# light-plate_leds_v1_0.net
KiCad netlist of a schematic drawn in EAGLE
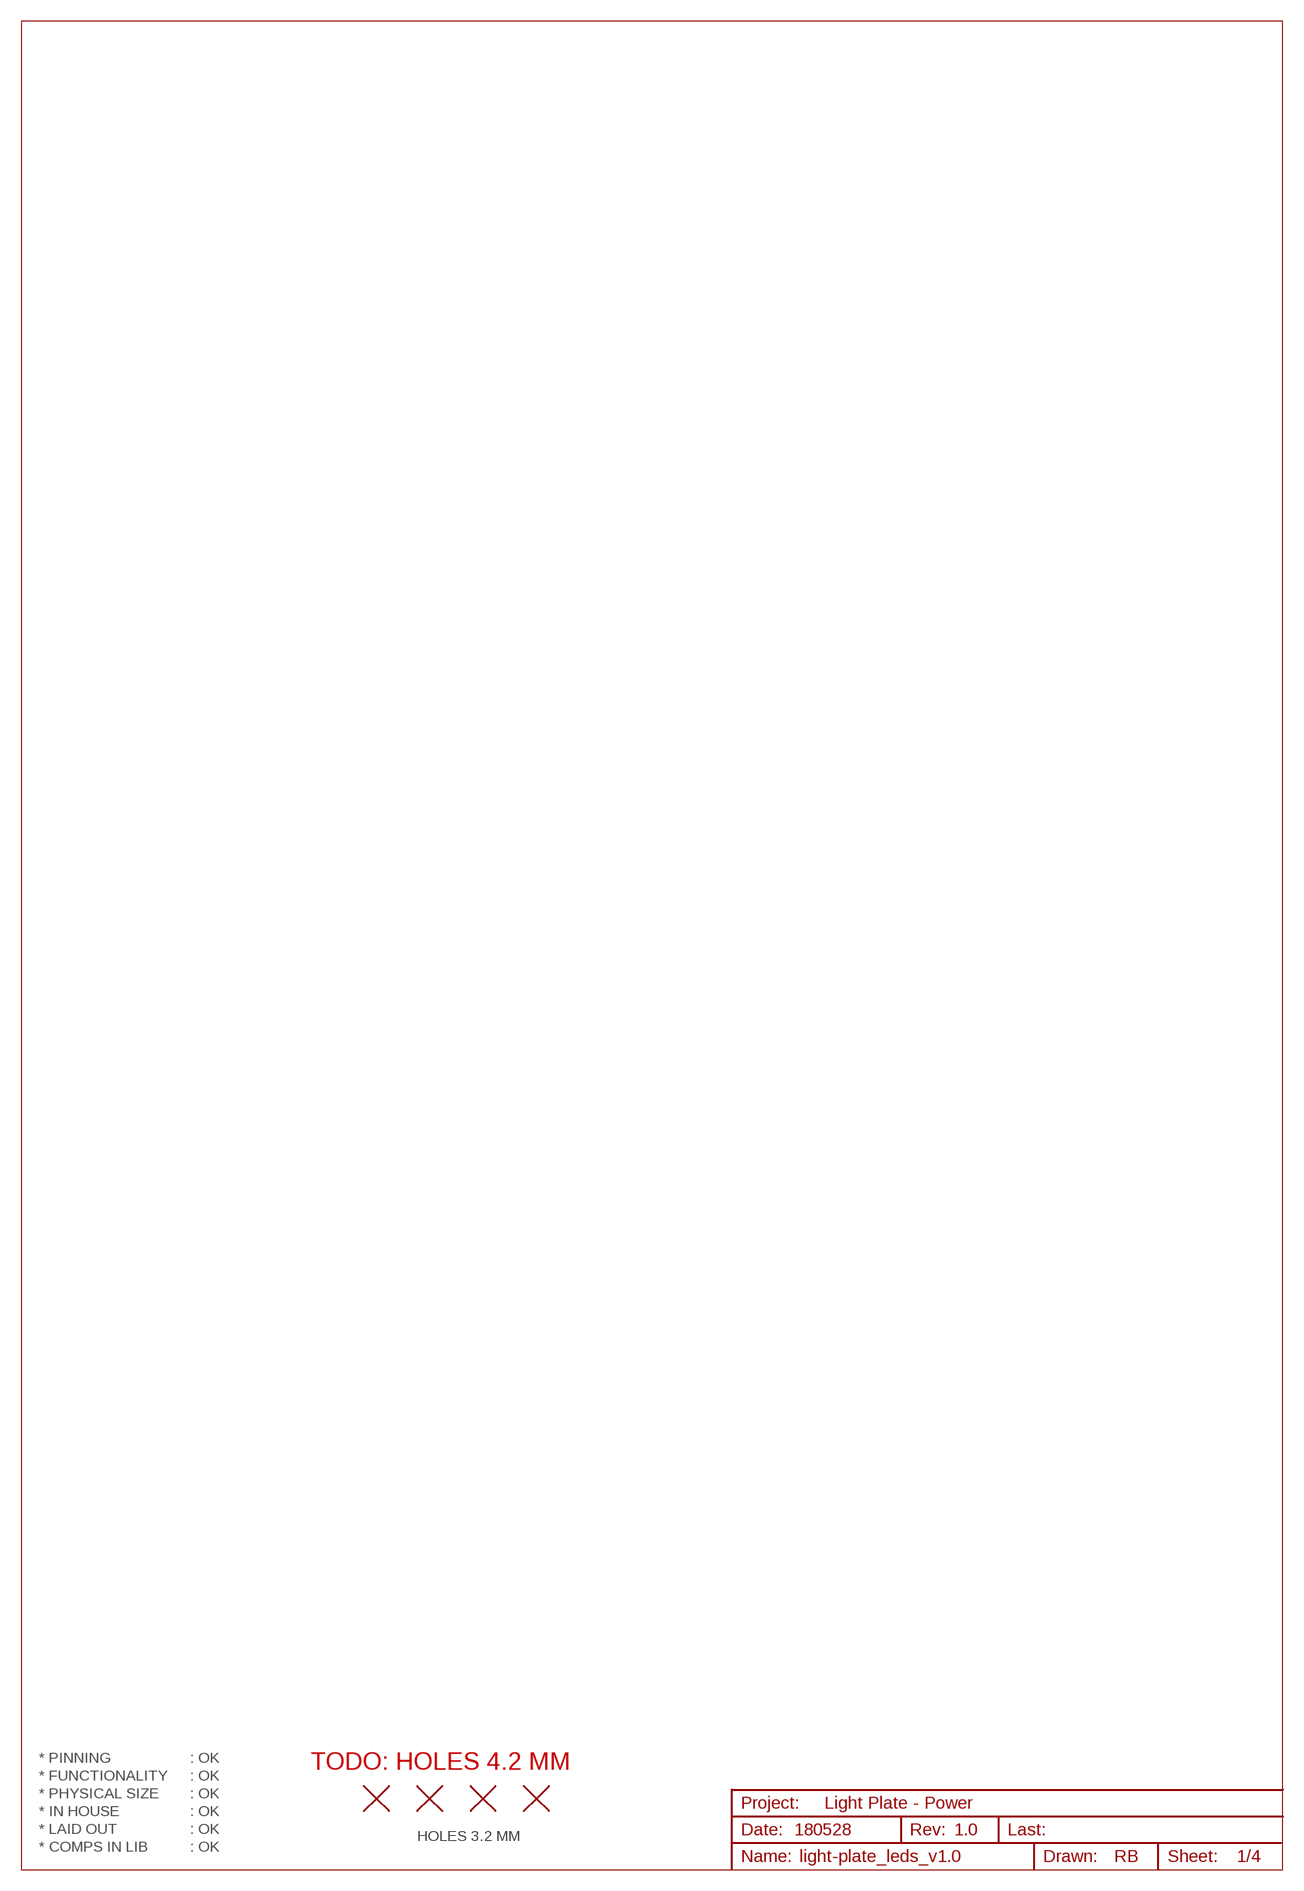
[diagram p0: schematic, sheet 1]
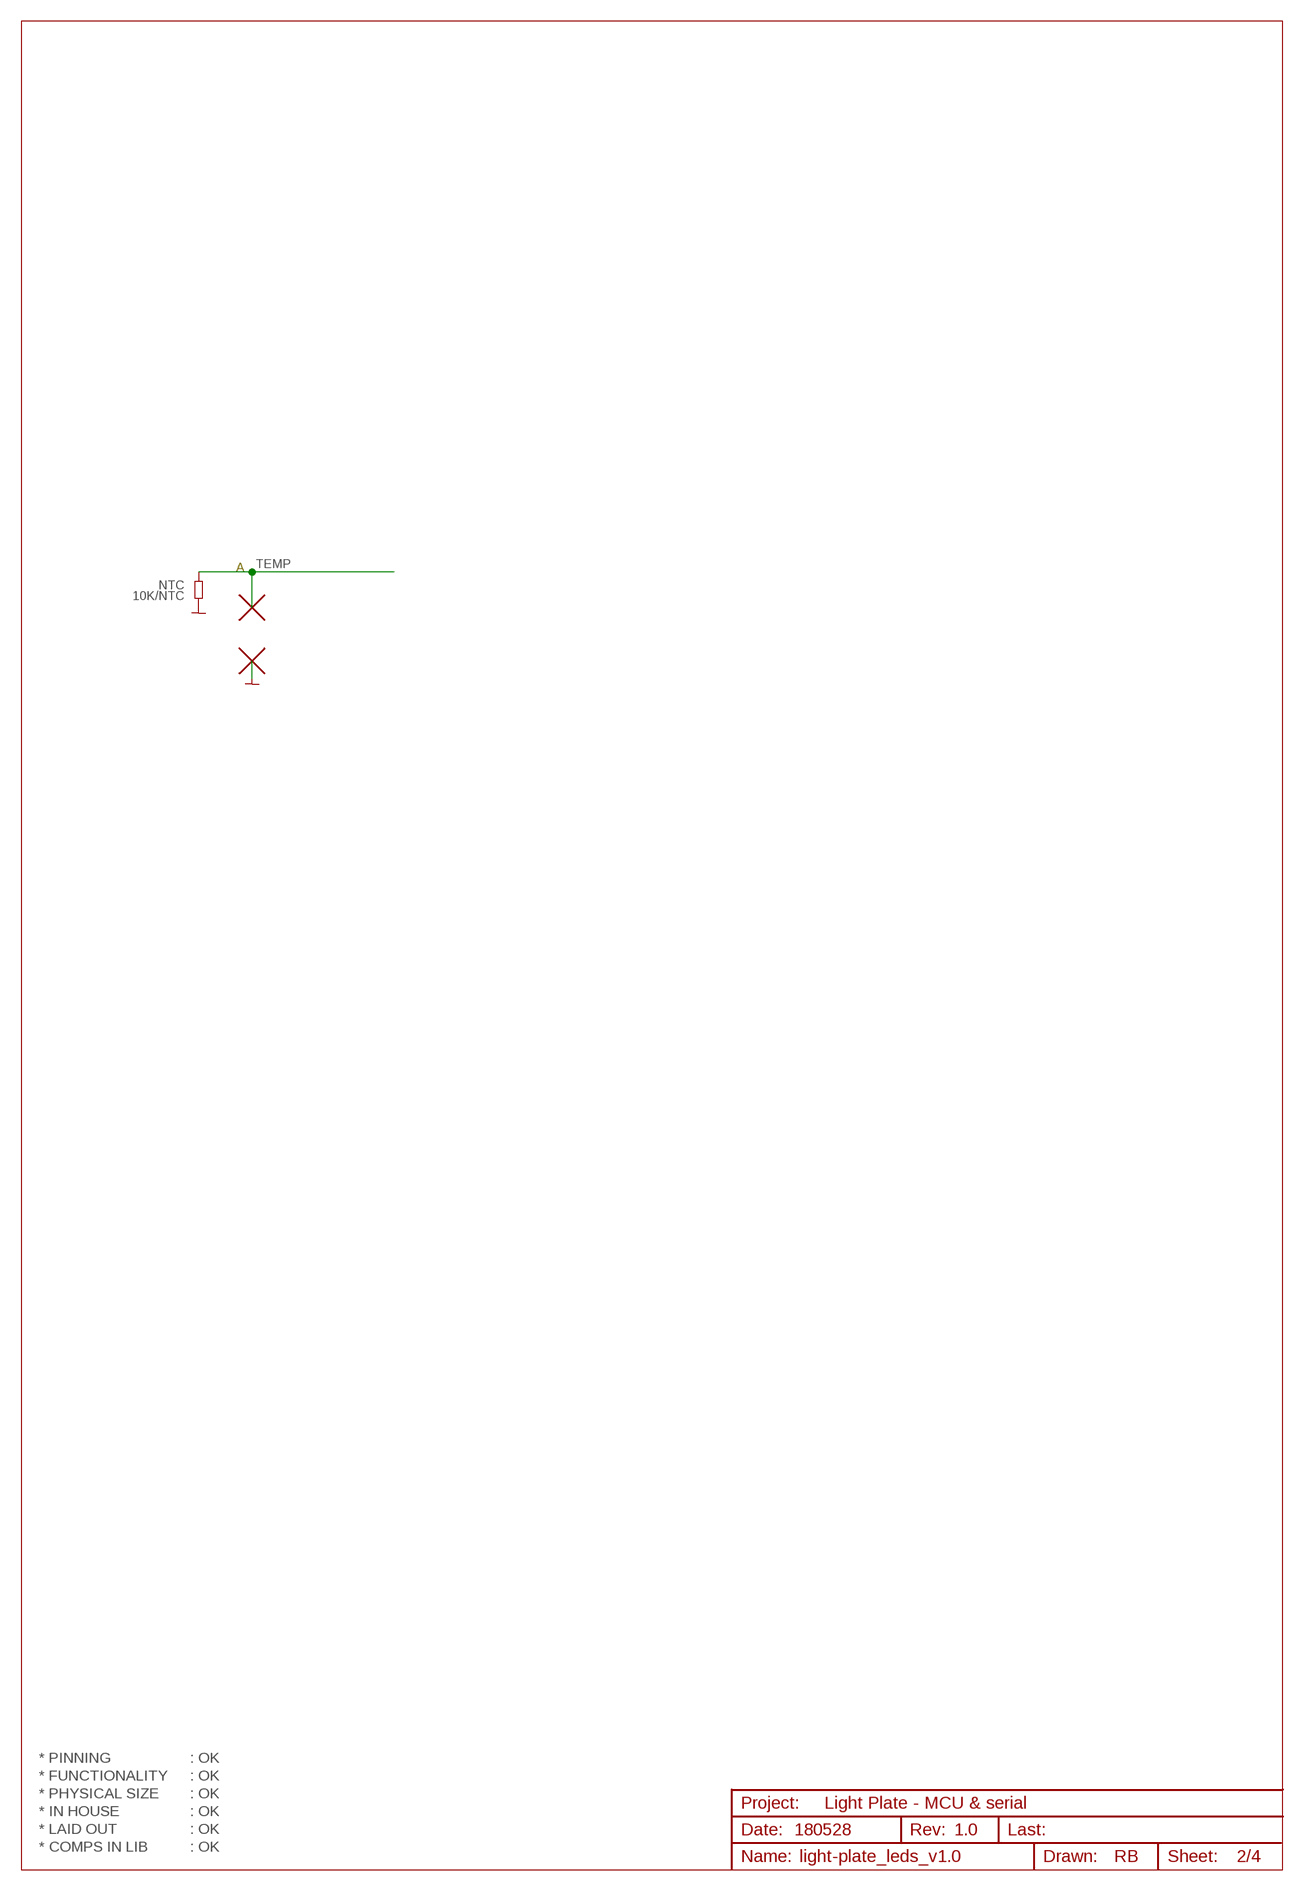
[diagram p1: schematic, sheet 2]
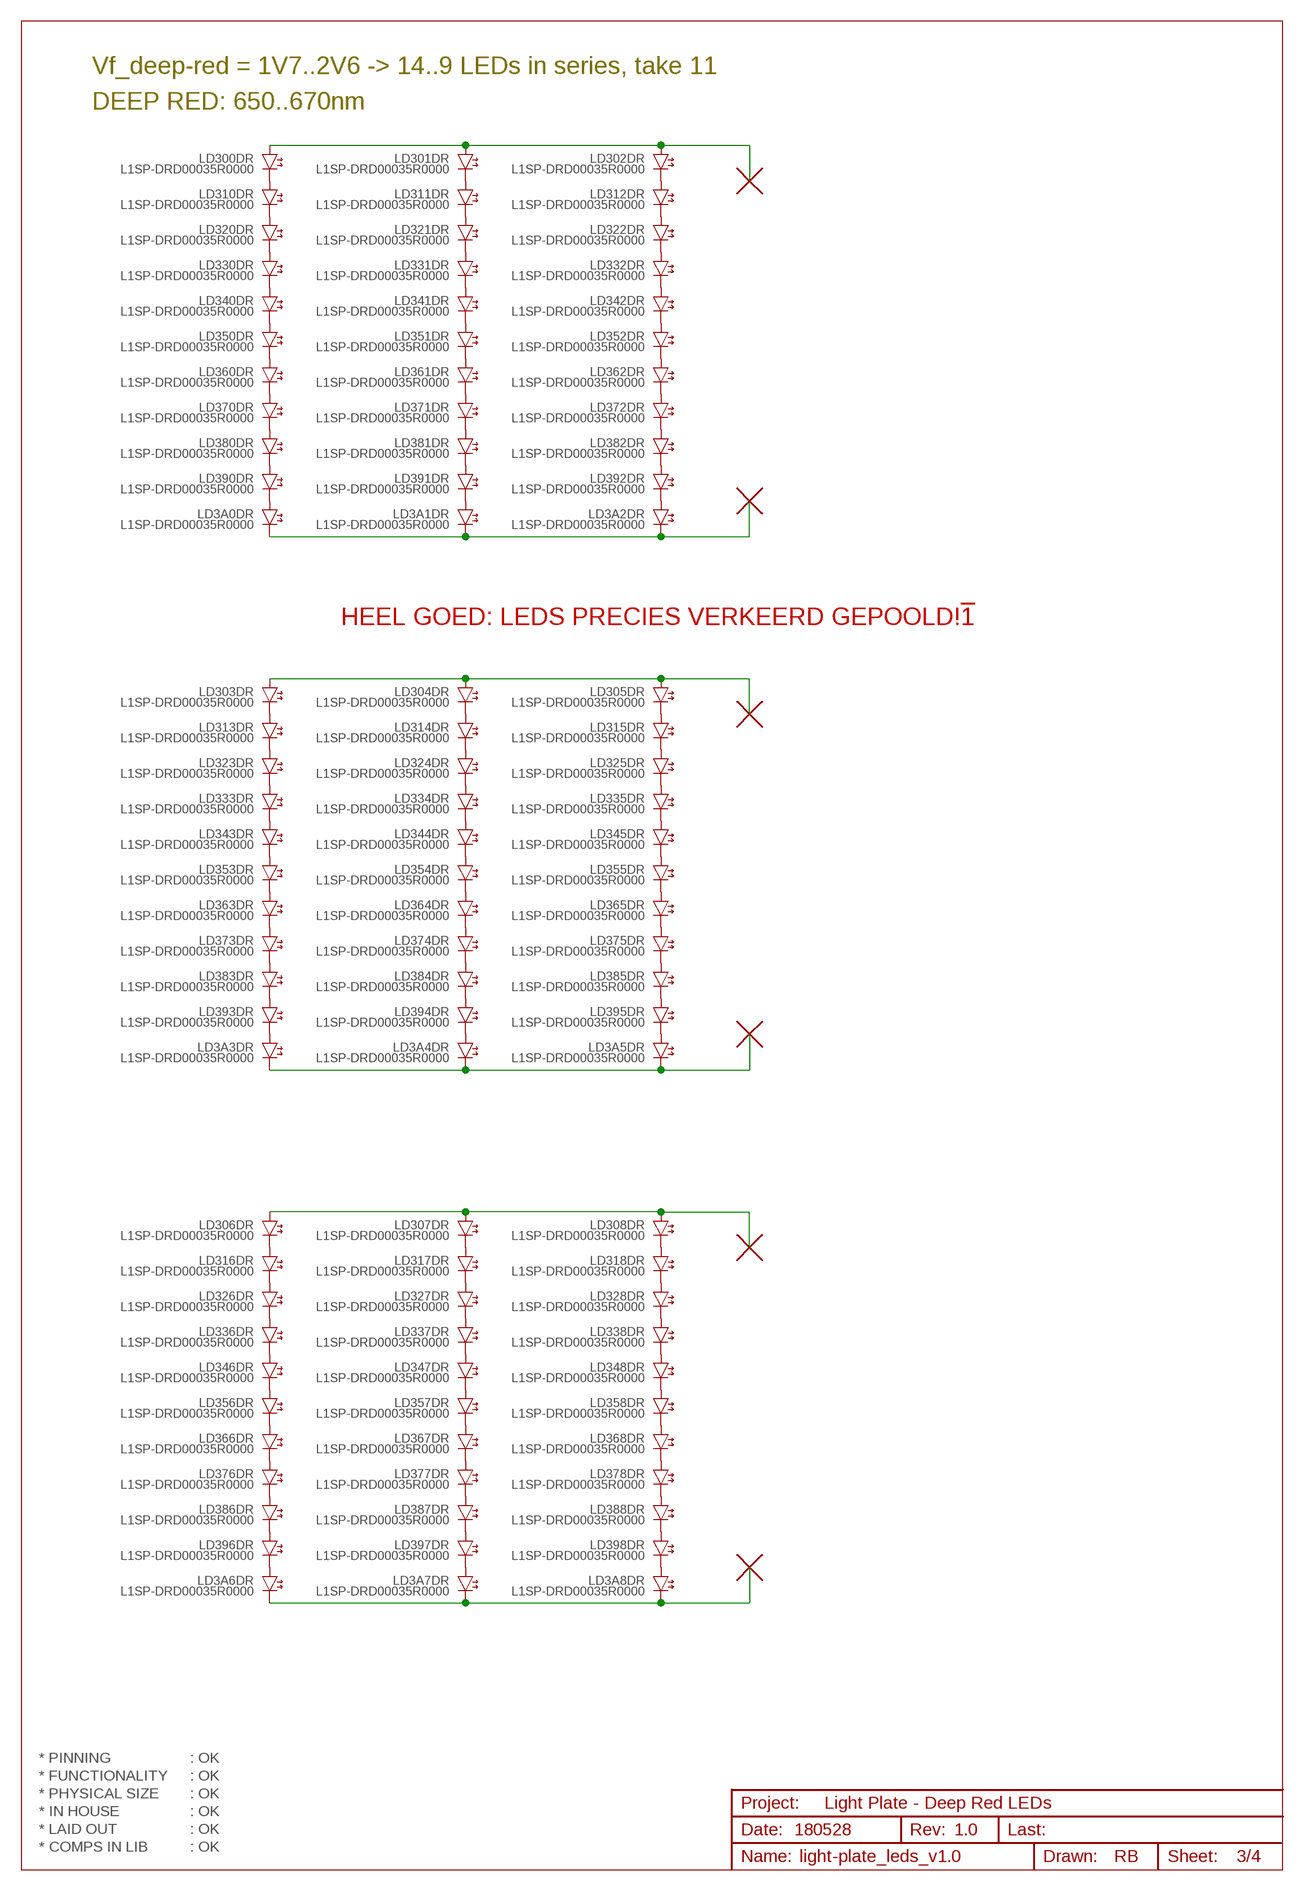
[diagram p2: schematic, sheet 3]
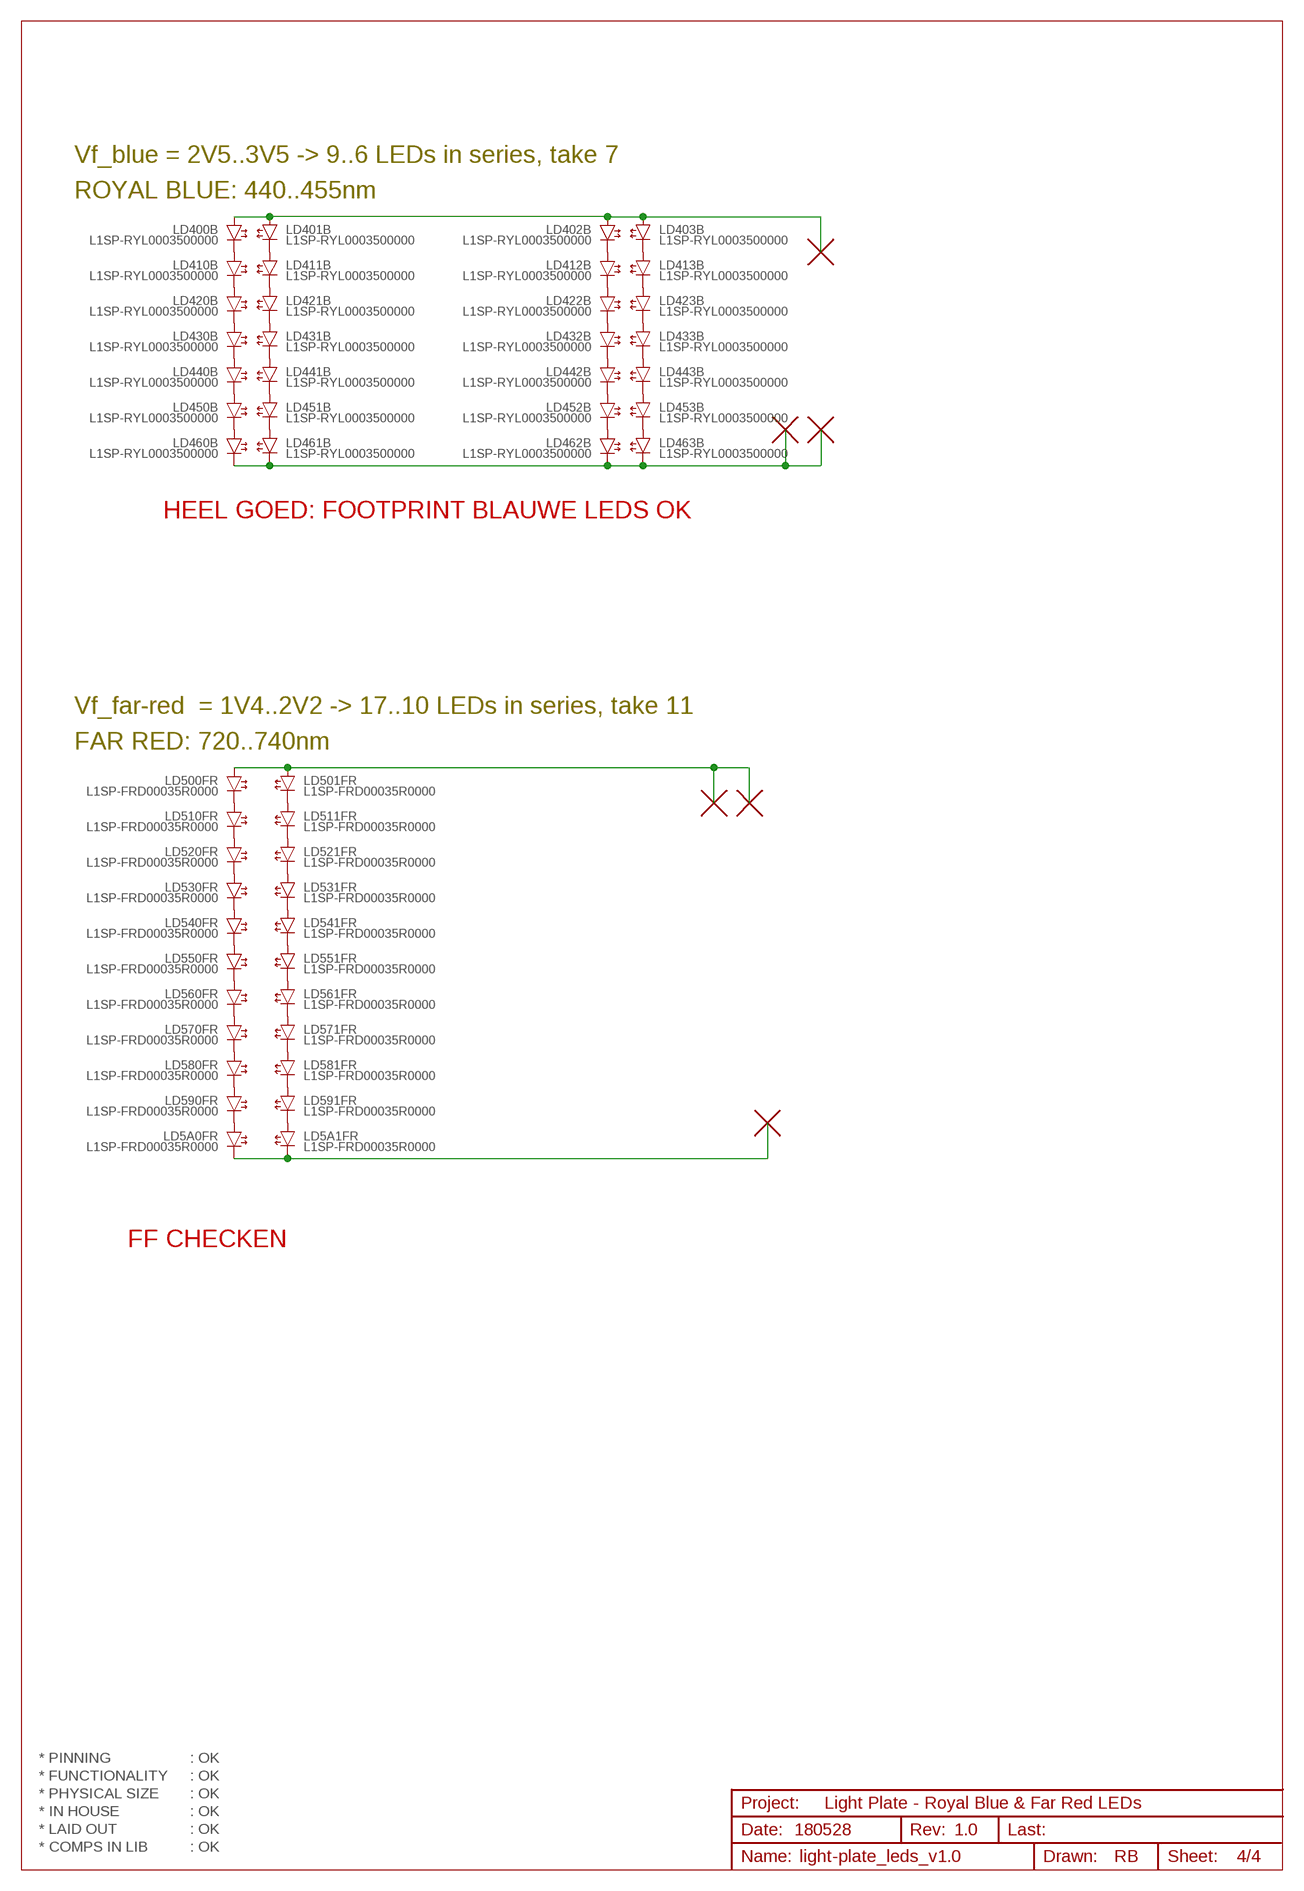
[diagram p3: schematic, sheet 4]

(export (version "E")
  (design (tool "Eeschema 10.0.6"))
  (components
    (comp (ref "H1")
      (value "HOLE_NPTH_3.2MM")
      (footprint "eagle-import:HOLE_NPTH_3.2MM")
      (libsource (lib "eagle-import") (part "HOLE_NPTH_3.2MM"))
    )
    (comp (ref "H2")
      (value "HOLE_NPTH_3.2MM")
      (footprint "eagle-import:HOLE_NPTH_3.2MM")
      (libsource (lib "eagle-import") (part "HOLE_NPTH_3.2MM"))
    )
    (comp (ref "H3")
      (value "HOLE_NPTH_3.2MM")
      (footprint "eagle-import:HOLE_NPTH_3.2MM")
      (libsource (lib "eagle-import") (part "HOLE_NPTH_3.2MM"))
    )
    (comp (ref "H4")
      (value "HOLE_NPTH_3.2MM")
      (footprint "eagle-import:HOLE_NPTH_3.2MM")
      (libsource (lib "eagle-import") (part "HOLE_NPTH_3.2MM"))
    )
    (comp (ref "H23")
      (value "PAD_ROUND_3.2MM")
      (footprint "eagle-import:PAD_ROUND_3.2MM")
      (libsource (lib "eagle-import") (part "PAD_ROUND_3.2MM"))
    )
    (comp (ref "H24")
      (value "PAD_ROUND_3.2MM")
      (footprint "eagle-import:PAD_ROUND_3.2MM")
      (libsource (lib "eagle-import") (part "PAD_ROUND_3.2MM"))
    )
    (comp (ref "H25")
      (value "PAD_ROUND_3.2MM")
      (footprint "eagle-import:PAD_ROUND_3.2MM")
      (libsource (lib "eagle-import") (part "PAD_ROUND_3.2MM"))
    )
    (comp (ref "H26")
      (value "PAD_ROUND_3.2MM")
      (footprint "eagle-import:PAD_ROUND_3.2MM")
      (libsource (lib "eagle-import") (part "PAD_ROUND_3.2MM"))
    )
    (comp (ref "H27")
      (value "PAD_ROUND_3.2MM")
      (footprint "eagle-import:PAD_ROUND_3.2MM")
      (libsource (lib "eagle-import") (part "PAD_ROUND_3.2MM"))
    )
    (comp (ref "H28")
      (value "PAD_ROUND_3.2MM")
      (footprint "eagle-import:PAD_ROUND_3.2MM")
      (libsource (lib "eagle-import") (part "PAD_ROUND_3.2MM"))
    )
    (comp (ref "LD5A0FR")
      (value "L1SP-FRD00035R0000")
      (footprint "eagle-import:LED_SMD_SUNPLUS35_REVERSED")
      (libsource (lib "eagle-import") (part "LED_SMD_SUNPLUS35_REVERSED"))
    )
    (comp (ref "LD5A1FR")
      (value "L1SP-FRD00035R0000")
      (footprint "eagle-import:LED_SMD_SUNPLUS35_REVERSED")
      (libsource (lib "eagle-import") (part "LED_SMD_SUNPLUS35_REVERSED"))
    )
    (comp (ref "LD400B")
      (value "L1SP-RYL0003500000")
      (footprint "eagle-import:LED_SMD_SUNPLUS35")
      (libsource (lib "eagle-import") (part "LED_SMD_SUNPLUS35"))
    )
    (comp (ref "LD401B")
      (value "L1SP-RYL0003500000")
      (footprint "eagle-import:LED_SMD_SUNPLUS35")
      (libsource (lib "eagle-import") (part "LED_SMD_SUNPLUS35"))
    )
    (comp (ref "LD402B")
      (value "L1SP-RYL0003500000")
      (footprint "eagle-import:LED_SMD_SUNPLUS35")
      (libsource (lib "eagle-import") (part "LED_SMD_SUNPLUS35"))
    )
    (comp (ref "LD403B")
      (value "L1SP-RYL0003500000")
      (footprint "eagle-import:LED_SMD_SUNPLUS35")
      (libsource (lib "eagle-import") (part "LED_SMD_SUNPLUS35"))
    )
    (comp (ref "LD410B")
      (value "L1SP-RYL0003500000")
      (footprint "eagle-import:LED_SMD_SUNPLUS35")
      (libsource (lib "eagle-import") (part "LED_SMD_SUNPLUS35"))
    )
    (comp (ref "LD411B")
      (value "L1SP-RYL0003500000")
      (footprint "eagle-import:LED_SMD_SUNPLUS35")
      (libsource (lib "eagle-import") (part "LED_SMD_SUNPLUS35"))
    )
    (comp (ref "LD412B")
      (value "L1SP-RYL0003500000")
      (footprint "eagle-import:LED_SMD_SUNPLUS35")
      (libsource (lib "eagle-import") (part "LED_SMD_SUNPLUS35"))
    )
    (comp (ref "LD413B")
      (value "L1SP-RYL0003500000")
      (footprint "eagle-import:LED_SMD_SUNPLUS35")
      (libsource (lib "eagle-import") (part "LED_SMD_SUNPLUS35"))
    )
    (comp (ref "LD420B")
      (value "L1SP-RYL0003500000")
      (footprint "eagle-import:LED_SMD_SUNPLUS35")
      (libsource (lib "eagle-import") (part "LED_SMD_SUNPLUS35"))
    )
    (comp (ref "LD421B")
      (value "L1SP-RYL0003500000")
      (footprint "eagle-import:LED_SMD_SUNPLUS35")
      (libsource (lib "eagle-import") (part "LED_SMD_SUNPLUS35"))
    )
    (comp (ref "LD422B")
      (value "L1SP-RYL0003500000")
      (footprint "eagle-import:LED_SMD_SUNPLUS35")
      (libsource (lib "eagle-import") (part "LED_SMD_SUNPLUS35"))
    )
    (comp (ref "LD423B")
      (value "L1SP-RYL0003500000")
      (footprint "eagle-import:LED_SMD_SUNPLUS35")
      (libsource (lib "eagle-import") (part "LED_SMD_SUNPLUS35"))
    )
    (comp (ref "LD430B")
      (value "L1SP-RYL0003500000")
      (footprint "eagle-import:LED_SMD_SUNPLUS35")
      (libsource (lib "eagle-import") (part "LED_SMD_SUNPLUS35"))
    )
    (comp (ref "LD431B")
      (value "L1SP-RYL0003500000")
      (footprint "eagle-import:LED_SMD_SUNPLUS35")
      (libsource (lib "eagle-import") (part "LED_SMD_SUNPLUS35"))
    )
    (comp (ref "LD432B")
      (value "L1SP-RYL0003500000")
      (footprint "eagle-import:LED_SMD_SUNPLUS35")
      (libsource (lib "eagle-import") (part "LED_SMD_SUNPLUS35"))
    )
    (comp (ref "LD433B")
      (value "L1SP-RYL0003500000")
      (footprint "eagle-import:LED_SMD_SUNPLUS35")
      (libsource (lib "eagle-import") (part "LED_SMD_SUNPLUS35"))
    )
    (comp (ref "LD440B")
      (value "L1SP-RYL0003500000")
      (footprint "eagle-import:LED_SMD_SUNPLUS35")
      (libsource (lib "eagle-import") (part "LED_SMD_SUNPLUS35"))
    )
    (comp (ref "LD441B")
      (value "L1SP-RYL0003500000")
      (footprint "eagle-import:LED_SMD_SUNPLUS35")
      (libsource (lib "eagle-import") (part "LED_SMD_SUNPLUS35"))
    )
    (comp (ref "LD442B")
      (value "L1SP-RYL0003500000")
      (footprint "eagle-import:LED_SMD_SUNPLUS35")
      (libsource (lib "eagle-import") (part "LED_SMD_SUNPLUS35"))
    )
    (comp (ref "LD443B")
      (value "L1SP-RYL0003500000")
      (footprint "eagle-import:LED_SMD_SUNPLUS35")
      (libsource (lib "eagle-import") (part "LED_SMD_SUNPLUS35"))
    )
    (comp (ref "LD450B")
      (value "L1SP-RYL0003500000")
      (footprint "eagle-import:LED_SMD_SUNPLUS35")
      (libsource (lib "eagle-import") (part "LED_SMD_SUNPLUS35"))
    )
    (comp (ref "LD451B")
      (value "L1SP-RYL0003500000")
      (footprint "eagle-import:LED_SMD_SUNPLUS35")
      (libsource (lib "eagle-import") (part "LED_SMD_SUNPLUS35"))
    )
    (comp (ref "LD452B")
      (value "L1SP-RYL0003500000")
      (footprint "eagle-import:LED_SMD_SUNPLUS35")
      (libsource (lib "eagle-import") (part "LED_SMD_SUNPLUS35"))
    )
    (comp (ref "LD453B")
      (value "L1SP-RYL0003500000")
      (footprint "eagle-import:LED_SMD_SUNPLUS35")
      (libsource (lib "eagle-import") (part "LED_SMD_SUNPLUS35"))
    )
    (comp (ref "LD460B")
      (value "L1SP-RYL0003500000")
      (footprint "eagle-import:LED_SMD_SUNPLUS35")
      (libsource (lib "eagle-import") (part "LED_SMD_SUNPLUS35"))
    )
    (comp (ref "LD461B")
      (value "L1SP-RYL0003500000")
      (footprint "eagle-import:LED_SMD_SUNPLUS35")
      (libsource (lib "eagle-import") (part "LED_SMD_SUNPLUS35"))
    )
    (comp (ref "LD462B")
      (value "L1SP-RYL0003500000")
      (footprint "eagle-import:LED_SMD_SUNPLUS35")
      (libsource (lib "eagle-import") (part "LED_SMD_SUNPLUS35"))
    )
    (comp (ref "LD463B")
      (value "L1SP-RYL0003500000")
      (footprint "eagle-import:LED_SMD_SUNPLUS35")
      (libsource (lib "eagle-import") (part "LED_SMD_SUNPLUS35"))
    )
    (comp (ref "LD500FR")
      (value "L1SP-FRD00035R0000")
      (footprint "eagle-import:LED_SMD_SUNPLUS35_REVERSED")
      (libsource (lib "eagle-import") (part "LED_SMD_SUNPLUS35_REVERSED"))
    )
    (comp (ref "LD501FR")
      (value "L1SP-FRD00035R0000")
      (footprint "eagle-import:LED_SMD_SUNPLUS35_REVERSED")
      (libsource (lib "eagle-import") (part "LED_SMD_SUNPLUS35_REVERSED"))
    )
    (comp (ref "LD510FR")
      (value "L1SP-FRD00035R0000")
      (footprint "eagle-import:LED_SMD_SUNPLUS35_REVERSED")
      (libsource (lib "eagle-import") (part "LED_SMD_SUNPLUS35_REVERSED"))
    )
    (comp (ref "LD511FR")
      (value "L1SP-FRD00035R0000")
      (footprint "eagle-import:LED_SMD_SUNPLUS35_REVERSED")
      (libsource (lib "eagle-import") (part "LED_SMD_SUNPLUS35_REVERSED"))
    )
    (comp (ref "LD520FR")
      (value "L1SP-FRD00035R0000")
      (footprint "eagle-import:LED_SMD_SUNPLUS35_REVERSED")
      (libsource (lib "eagle-import") (part "LED_SMD_SUNPLUS35_REVERSED"))
    )
    (comp (ref "LD521FR")
      (value "L1SP-FRD00035R0000")
      (footprint "eagle-import:LED_SMD_SUNPLUS35_REVERSED")
      (libsource (lib "eagle-import") (part "LED_SMD_SUNPLUS35_REVERSED"))
    )
    (comp (ref "LD530FR")
      (value "L1SP-FRD00035R0000")
      (footprint "eagle-import:LED_SMD_SUNPLUS35_REVERSED")
      (libsource (lib "eagle-import") (part "LED_SMD_SUNPLUS35_REVERSED"))
    )
    (comp (ref "LD531FR")
      (value "L1SP-FRD00035R0000")
      (footprint "eagle-import:LED_SMD_SUNPLUS35_REVERSED")
      (libsource (lib "eagle-import") (part "LED_SMD_SUNPLUS35_REVERSED"))
    )
    (comp (ref "LD540FR")
      (value "L1SP-FRD00035R0000")
      (footprint "eagle-import:LED_SMD_SUNPLUS35_REVERSED")
      (libsource (lib "eagle-import") (part "LED_SMD_SUNPLUS35_REVERSED"))
    )
    (comp (ref "LD541FR")
      (value "L1SP-FRD00035R0000")
      (footprint "eagle-import:LED_SMD_SUNPLUS35_REVERSED")
      (libsource (lib "eagle-import") (part "LED_SMD_SUNPLUS35_REVERSED"))
    )
    (comp (ref "LD550FR")
      (value "L1SP-FRD00035R0000")
      (footprint "eagle-import:LED_SMD_SUNPLUS35_REVERSED")
      (libsource (lib "eagle-import") (part "LED_SMD_SUNPLUS35_REVERSED"))
    )
    (comp (ref "LD551FR")
      (value "L1SP-FRD00035R0000")
      (footprint "eagle-import:LED_SMD_SUNPLUS35_REVERSED")
      (libsource (lib "eagle-import") (part "LED_SMD_SUNPLUS35_REVERSED"))
    )
    (comp (ref "LD560FR")
      (value "L1SP-FRD00035R0000")
      (footprint "eagle-import:LED_SMD_SUNPLUS35_REVERSED")
      (libsource (lib "eagle-import") (part "LED_SMD_SUNPLUS35_REVERSED"))
    )
    (comp (ref "LD561FR")
      (value "L1SP-FRD00035R0000")
      (footprint "eagle-import:LED_SMD_SUNPLUS35_REVERSED")
      (libsource (lib "eagle-import") (part "LED_SMD_SUNPLUS35_REVERSED"))
    )
    (comp (ref "LD570FR")
      (value "L1SP-FRD00035R0000")
      (footprint "eagle-import:LED_SMD_SUNPLUS35_REVERSED")
      (libsource (lib "eagle-import") (part "LED_SMD_SUNPLUS35_REVERSED"))
    )
    (comp (ref "LD571FR")
      (value "L1SP-FRD00035R0000")
      (footprint "eagle-import:LED_SMD_SUNPLUS35_REVERSED")
      (libsource (lib "eagle-import") (part "LED_SMD_SUNPLUS35_REVERSED"))
    )
    (comp (ref "LD580FR")
      (value "L1SP-FRD00035R0000")
      (footprint "eagle-import:LED_SMD_SUNPLUS35_REVERSED")
      (libsource (lib "eagle-import") (part "LED_SMD_SUNPLUS35_REVERSED"))
    )
    (comp (ref "LD581FR")
      (value "L1SP-FRD00035R0000")
      (footprint "eagle-import:LED_SMD_SUNPLUS35_REVERSED")
      (libsource (lib "eagle-import") (part "LED_SMD_SUNPLUS35_REVERSED"))
    )
    (comp (ref "LD590FR")
      (value "L1SP-FRD00035R0000")
      (footprint "eagle-import:LED_SMD_SUNPLUS35_REVERSED")
      (libsource (lib "eagle-import") (part "LED_SMD_SUNPLUS35_REVERSED"))
    )
    (comp (ref "LD591FR")
      (value "L1SP-FRD00035R0000")
      (footprint "eagle-import:LED_SMD_SUNPLUS35_REVERSED")
      (libsource (lib "eagle-import") (part "LED_SMD_SUNPLUS35_REVERSED"))
    )
    (comp (ref "H11")
      (value "PAD_ROUND_1.6MM")
      (footprint "eagle-import:PAD_ROUND_1.6MM")
      (libsource (lib "eagle-import") (part "PAD_ROUND_1.6MM"))
    )
    (comp (ref "H12")
      (value "PAD_ROUND_1.6MM")
      (footprint "eagle-import:PAD_ROUND_1.6MM")
      (libsource (lib "eagle-import") (part "PAD_ROUND_1.6MM"))
    )
    (comp (ref "NTC")
      (value "10K/NTC")
      (footprint "eagle-import:RES0603")
      (libsource (lib "eagle-import") (part "RES0603"))
    )
    (comp (ref "H17")
      (value "PAD_ROUND_3.2MM")
      (footprint "eagle-import:PAD_ROUND_3.2MM")
      (libsource (lib "eagle-import") (part "PAD_ROUND_3.2MM"))
    )
    (comp (ref "H18")
      (value "PAD_ROUND_3.2MM")
      (footprint "eagle-import:PAD_ROUND_3.2MM")
      (libsource (lib "eagle-import") (part "PAD_ROUND_3.2MM"))
    )
    (comp (ref "H19")
      (value "PAD_ROUND_3.2MM")
      (footprint "eagle-import:PAD_ROUND_3.2MM")
      (libsource (lib "eagle-import") (part "PAD_ROUND_3.2MM"))
    )
    (comp (ref "H20")
      (value "PAD_ROUND_3.2MM")
      (footprint "eagle-import:PAD_ROUND_3.2MM")
      (libsource (lib "eagle-import") (part "PAD_ROUND_3.2MM"))
    )
    (comp (ref "H21")
      (value "PAD_ROUND_3.2MM")
      (footprint "eagle-import:PAD_ROUND_3.2MM")
      (libsource (lib "eagle-import") (part "PAD_ROUND_3.2MM"))
    )
    (comp (ref "H22")
      (value "PAD_ROUND_3.2MM")
      (footprint "eagle-import:PAD_ROUND_3.2MM")
      (libsource (lib "eagle-import") (part "PAD_ROUND_3.2MM"))
    )
    (comp (ref "LD3A0DR")
      (value "L1SP-DRD00035R0000")
      (footprint "eagle-import:LED_SMD_SUNPLUS35_REVERSED")
      (libsource (lib "eagle-import") (part "LED_SMD_SUNPLUS35_REVERSED"))
    )
    (comp (ref "LD3A1DR")
      (value "L1SP-DRD00035R0000")
      (footprint "eagle-import:LED_SMD_SUNPLUS35_REVERSED")
      (libsource (lib "eagle-import") (part "LED_SMD_SUNPLUS35_REVERSED"))
    )
    (comp (ref "LD3A2DR")
      (value "L1SP-DRD00035R0000")
      (footprint "eagle-import:LED_SMD_SUNPLUS35_REVERSED")
      (libsource (lib "eagle-import") (part "LED_SMD_SUNPLUS35_REVERSED"))
    )
    (comp (ref "LD3A3DR")
      (value "L1SP-DRD00035R0000")
      (footprint "eagle-import:LED_SMD_SUNPLUS35_REVERSED")
      (libsource (lib "eagle-import") (part "LED_SMD_SUNPLUS35_REVERSED"))
    )
    (comp (ref "LD3A4DR")
      (value "L1SP-DRD00035R0000")
      (footprint "eagle-import:LED_SMD_SUNPLUS35_REVERSED")
      (libsource (lib "eagle-import") (part "LED_SMD_SUNPLUS35_REVERSED"))
    )
    (comp (ref "LD3A5DR")
      (value "L1SP-DRD00035R0000")
      (footprint "eagle-import:LED_SMD_SUNPLUS35_REVERSED")
      (libsource (lib "eagle-import") (part "LED_SMD_SUNPLUS35_REVERSED"))
    )
    (comp (ref "LD3A6DR")
      (value "L1SP-DRD00035R0000")
      (footprint "eagle-import:LED_SMD_SUNPLUS35_REVERSED")
      (libsource (lib "eagle-import") (part "LED_SMD_SUNPLUS35_REVERSED"))
    )
    (comp (ref "LD3A7DR")
      (value "L1SP-DRD00035R0000")
      (footprint "eagle-import:LED_SMD_SUNPLUS35_REVERSED")
      (libsource (lib "eagle-import") (part "LED_SMD_SUNPLUS35_REVERSED"))
    )
    (comp (ref "LD3A8DR")
      (value "L1SP-DRD00035R0000")
      (footprint "eagle-import:LED_SMD_SUNPLUS35_REVERSED")
      (libsource (lib "eagle-import") (part "LED_SMD_SUNPLUS35_REVERSED"))
    )
    (comp (ref "LD300DR")
      (value "L1SP-DRD00035R0000")
      (footprint "eagle-import:LED_SMD_SUNPLUS35_REVERSED")
      (libsource (lib "eagle-import") (part "LED_SMD_SUNPLUS35_REVERSED"))
    )
    (comp (ref "LD301DR")
      (value "L1SP-DRD00035R0000")
      (footprint "eagle-import:LED_SMD_SUNPLUS35_REVERSED")
      (libsource (lib "eagle-import") (part "LED_SMD_SUNPLUS35_REVERSED"))
    )
    (comp (ref "LD302DR")
      (value "L1SP-DRD00035R0000")
      (footprint "eagle-import:LED_SMD_SUNPLUS35_REVERSED")
      (libsource (lib "eagle-import") (part "LED_SMD_SUNPLUS35_REVERSED"))
    )
    (comp (ref "LD303DR")
      (value "L1SP-DRD00035R0000")
      (footprint "eagle-import:LED_SMD_SUNPLUS35_REVERSED")
      (libsource (lib "eagle-import") (part "LED_SMD_SUNPLUS35_REVERSED"))
    )
    (comp (ref "LD304DR")
      (value "L1SP-DRD00035R0000")
      (footprint "eagle-import:LED_SMD_SUNPLUS35_REVERSED")
      (libsource (lib "eagle-import") (part "LED_SMD_SUNPLUS35_REVERSED"))
    )
    (comp (ref "LD305DR")
      (value "L1SP-DRD00035R0000")
      (footprint "eagle-import:LED_SMD_SUNPLUS35_REVERSED")
      (libsource (lib "eagle-import") (part "LED_SMD_SUNPLUS35_REVERSED"))
    )
    (comp (ref "LD306DR")
      (value "L1SP-DRD00035R0000")
      (footprint "eagle-import:LED_SMD_SUNPLUS35_REVERSED")
      (libsource (lib "eagle-import") (part "LED_SMD_SUNPLUS35_REVERSED"))
    )
    (comp (ref "LD307DR")
      (value "L1SP-DRD00035R0000")
      (footprint "eagle-import:LED_SMD_SUNPLUS35_REVERSED")
      (libsource (lib "eagle-import") (part "LED_SMD_SUNPLUS35_REVERSED"))
    )
    (comp (ref "LD308DR")
      (value "L1SP-DRD00035R0000")
      (footprint "eagle-import:LED_SMD_SUNPLUS35_REVERSED")
      (libsource (lib "eagle-import") (part "LED_SMD_SUNPLUS35_REVERSED"))
    )
    (comp (ref "LD310DR")
      (value "L1SP-DRD00035R0000")
      (footprint "eagle-import:LED_SMD_SUNPLUS35_REVERSED")
      (libsource (lib "eagle-import") (part "LED_SMD_SUNPLUS35_REVERSED"))
    )
    (comp (ref "LD311DR")
      (value "L1SP-DRD00035R0000")
      (footprint "eagle-import:LED_SMD_SUNPLUS35_REVERSED")
      (libsource (lib "eagle-import") (part "LED_SMD_SUNPLUS35_REVERSED"))
    )
    (comp (ref "LD312DR")
      (value "L1SP-DRD00035R0000")
      (footprint "eagle-import:LED_SMD_SUNPLUS35_REVERSED")
      (libsource (lib "eagle-import") (part "LED_SMD_SUNPLUS35_REVERSED"))
    )
    (comp (ref "LD313DR")
      (value "L1SP-DRD00035R0000")
      (footprint "eagle-import:LED_SMD_SUNPLUS35_REVERSED")
      (libsource (lib "eagle-import") (part "LED_SMD_SUNPLUS35_REVERSED"))
    )
    (comp (ref "LD314DR")
      (value "L1SP-DRD00035R0000")
      (footprint "eagle-import:LED_SMD_SUNPLUS35_REVERSED")
      (libsource (lib "eagle-import") (part "LED_SMD_SUNPLUS35_REVERSED"))
    )
    (comp (ref "LD315DR")
      (value "L1SP-DRD00035R0000")
      (footprint "eagle-import:LED_SMD_SUNPLUS35_REVERSED")
      (libsource (lib "eagle-import") (part "LED_SMD_SUNPLUS35_REVERSED"))
    )
    (comp (ref "LD316DR")
      (value "L1SP-DRD00035R0000")
      (footprint "eagle-import:LED_SMD_SUNPLUS35_REVERSED")
      (libsource (lib "eagle-import") (part "LED_SMD_SUNPLUS35_REVERSED"))
    )
    (comp (ref "LD317DR")
      (value "L1SP-DRD00035R0000")
      (footprint "eagle-import:LED_SMD_SUNPLUS35_REVERSED")
      (libsource (lib "eagle-import") (part "LED_SMD_SUNPLUS35_REVERSED"))
    )
    (comp (ref "LD318DR")
      (value "L1SP-DRD00035R0000")
      (footprint "eagle-import:LED_SMD_SUNPLUS35_REVERSED")
      (libsource (lib "eagle-import") (part "LED_SMD_SUNPLUS35_REVERSED"))
    )
    (comp (ref "LD320DR")
      (value "L1SP-DRD00035R0000")
      (footprint "eagle-import:LED_SMD_SUNPLUS35_REVERSED")
      (libsource (lib "eagle-import") (part "LED_SMD_SUNPLUS35_REVERSED"))
    )
    (comp (ref "LD321DR")
      (value "L1SP-DRD00035R0000")
      (footprint "eagle-import:LED_SMD_SUNPLUS35_REVERSED")
      (libsource (lib "eagle-import") (part "LED_SMD_SUNPLUS35_REVERSED"))
    )
    (comp (ref "LD322DR")
      (value "L1SP-DRD00035R0000")
      (footprint "eagle-import:LED_SMD_SUNPLUS35_REVERSED")
      (libsource (lib "eagle-import") (part "LED_SMD_SUNPLUS35_REVERSED"))
    )
    (comp (ref "LD323DR")
      (value "L1SP-DRD00035R0000")
      (footprint "eagle-import:LED_SMD_SUNPLUS35_REVERSED")
      (libsource (lib "eagle-import") (part "LED_SMD_SUNPLUS35_REVERSED"))
    )
    (comp (ref "LD324DR")
      (value "L1SP-DRD00035R0000")
      (footprint "eagle-import:LED_SMD_SUNPLUS35_REVERSED")
      (libsource (lib "eagle-import") (part "LED_SMD_SUNPLUS35_REVERSED"))
    )
    (comp (ref "LD325DR")
      (value "L1SP-DRD00035R0000")
      (footprint "eagle-import:LED_SMD_SUNPLUS35_REVERSED")
      (libsource (lib "eagle-import") (part "LED_SMD_SUNPLUS35_REVERSED"))
    )
    (comp (ref "LD326DR")
      (value "L1SP-DRD00035R0000")
      (footprint "eagle-import:LED_SMD_SUNPLUS35_REVERSED")
      (libsource (lib "eagle-import") (part "LED_SMD_SUNPLUS35_REVERSED"))
    )
    (comp (ref "LD327DR")
      (value "L1SP-DRD00035R0000")
      (footprint "eagle-import:LED_SMD_SUNPLUS35_REVERSED")
      (libsource (lib "eagle-import") (part "LED_SMD_SUNPLUS35_REVERSED"))
    )
    (comp (ref "LD328DR")
      (value "L1SP-DRD00035R0000")
      (footprint "eagle-import:LED_SMD_SUNPLUS35_REVERSED")
      (libsource (lib "eagle-import") (part "LED_SMD_SUNPLUS35_REVERSED"))
    )
    (comp (ref "LD330DR")
      (value "L1SP-DRD00035R0000")
      (footprint "eagle-import:LED_SMD_SUNPLUS35_REVERSED")
      (libsource (lib "eagle-import") (part "LED_SMD_SUNPLUS35_REVERSED"))
    )
    (comp (ref "LD331DR")
      (value "L1SP-DRD00035R0000")
      (footprint "eagle-import:LED_SMD_SUNPLUS35_REVERSED")
      (libsource (lib "eagle-import") (part "LED_SMD_SUNPLUS35_REVERSED"))
    )
    (comp (ref "LD332DR")
      (value "L1SP-DRD00035R0000")
      (footprint "eagle-import:LED_SMD_SUNPLUS35_REVERSED")
      (libsource (lib "eagle-import") (part "LED_SMD_SUNPLUS35_REVERSED"))
    )
    (comp (ref "LD333DR")
      (value "L1SP-DRD00035R0000")
      (footprint "eagle-import:LED_SMD_SUNPLUS35_REVERSED")
      (libsource (lib "eagle-import") (part "LED_SMD_SUNPLUS35_REVERSED"))
    )
    (comp (ref "LD334DR")
      (value "L1SP-DRD00035R0000")
      (footprint "eagle-import:LED_SMD_SUNPLUS35_REVERSED")
      (libsource (lib "eagle-import") (part "LED_SMD_SUNPLUS35_REVERSED"))
    )
    (comp (ref "LD335DR")
      (value "L1SP-DRD00035R0000")
      (footprint "eagle-import:LED_SMD_SUNPLUS35_REVERSED")
      (libsource (lib "eagle-import") (part "LED_SMD_SUNPLUS35_REVERSED"))
    )
    (comp (ref "LD336DR")
      (value "L1SP-DRD00035R0000")
      (footprint "eagle-import:LED_SMD_SUNPLUS35_REVERSED")
      (libsource (lib "eagle-import") (part "LED_SMD_SUNPLUS35_REVERSED"))
    )
    (comp (ref "LD337DR")
      (value "L1SP-DRD00035R0000")
      (footprint "eagle-import:LED_SMD_SUNPLUS35_REVERSED")
      (libsource (lib "eagle-import") (part "LED_SMD_SUNPLUS35_REVERSED"))
    )
    (comp (ref "LD338DR")
      (value "L1SP-DRD00035R0000")
      (footprint "eagle-import:LED_SMD_SUNPLUS35_REVERSED")
      (libsource (lib "eagle-import") (part "LED_SMD_SUNPLUS35_REVERSED"))
    )
    (comp (ref "LD340DR")
      (value "L1SP-DRD00035R0000")
      (footprint "eagle-import:LED_SMD_SUNPLUS35_REVERSED")
      (libsource (lib "eagle-import") (part "LED_SMD_SUNPLUS35_REVERSED"))
    )
    (comp (ref "LD341DR")
      (value "L1SP-DRD00035R0000")
      (footprint "eagle-import:LED_SMD_SUNPLUS35_REVERSED")
      (libsource (lib "eagle-import") (part "LED_SMD_SUNPLUS35_REVERSED"))
    )
    (comp (ref "LD342DR")
      (value "L1SP-DRD00035R0000")
      (footprint "eagle-import:LED_SMD_SUNPLUS35_REVERSED")
      (libsource (lib "eagle-import") (part "LED_SMD_SUNPLUS35_REVERSED"))
    )
    (comp (ref "LD343DR")
      (value "L1SP-DRD00035R0000")
      (footprint "eagle-import:LED_SMD_SUNPLUS35_REVERSED")
      (libsource (lib "eagle-import") (part "LED_SMD_SUNPLUS35_REVERSED"))
    )
    (comp (ref "LD344DR")
      (value "L1SP-DRD00035R0000")
      (footprint "eagle-import:LED_SMD_SUNPLUS35_REVERSED")
      (libsource (lib "eagle-import") (part "LED_SMD_SUNPLUS35_REVERSED"))
    )
    (comp (ref "LD345DR")
      (value "L1SP-DRD00035R0000")
      (footprint "eagle-import:LED_SMD_SUNPLUS35_REVERSED")
      (libsource (lib "eagle-import") (part "LED_SMD_SUNPLUS35_REVERSED"))
    )
    (comp (ref "LD346DR")
      (value "L1SP-DRD00035R0000")
      (footprint "eagle-import:LED_SMD_SUNPLUS35_REVERSED")
      (libsource (lib "eagle-import") (part "LED_SMD_SUNPLUS35_REVERSED"))
    )
    (comp (ref "LD347DR")
      (value "L1SP-DRD00035R0000")
      (footprint "eagle-import:LED_SMD_SUNPLUS35_REVERSED")
      (libsource (lib "eagle-import") (part "LED_SMD_SUNPLUS35_REVERSED"))
    )
    (comp (ref "LD348DR")
      (value "L1SP-DRD00035R0000")
      (footprint "eagle-import:LED_SMD_SUNPLUS35_REVERSED")
      (libsource (lib "eagle-import") (part "LED_SMD_SUNPLUS35_REVERSED"))
    )
    (comp (ref "LD350DR")
      (value "L1SP-DRD00035R0000")
      (footprint "eagle-import:LED_SMD_SUNPLUS35_REVERSED")
      (libsource (lib "eagle-import") (part "LED_SMD_SUNPLUS35_REVERSED"))
    )
    (comp (ref "LD351DR")
      (value "L1SP-DRD00035R0000")
      (footprint "eagle-import:LED_SMD_SUNPLUS35_REVERSED")
      (libsource (lib "eagle-import") (part "LED_SMD_SUNPLUS35_REVERSED"))
    )
    (comp (ref "LD352DR")
      (value "L1SP-DRD00035R0000")
      (footprint "eagle-import:LED_SMD_SUNPLUS35_REVERSED")
      (libsource (lib "eagle-import") (part "LED_SMD_SUNPLUS35_REVERSED"))
    )
    (comp (ref "LD353DR")
      (value "L1SP-DRD00035R0000")
      (footprint "eagle-import:LED_SMD_SUNPLUS35_REVERSED")
      (libsource (lib "eagle-import") (part "LED_SMD_SUNPLUS35_REVERSED"))
    )
    (comp (ref "LD354DR")
      (value "L1SP-DRD00035R0000")
      (footprint "eagle-import:LED_SMD_SUNPLUS35_REVERSED")
      (libsource (lib "eagle-import") (part "LED_SMD_SUNPLUS35_REVERSED"))
    )
    (comp (ref "LD355DR")
      (value "L1SP-DRD00035R0000")
      (footprint "eagle-import:LED_SMD_SUNPLUS35_REVERSED")
      (libsource (lib "eagle-import") (part "LED_SMD_SUNPLUS35_REVERSED"))
    )
    (comp (ref "LD356DR")
      (value "L1SP-DRD00035R0000")
      (footprint "eagle-import:LED_SMD_SUNPLUS35_REVERSED")
      (libsource (lib "eagle-import") (part "LED_SMD_SUNPLUS35_REVERSED"))
    )
    (comp (ref "LD357DR")
      (value "L1SP-DRD00035R0000")
      (footprint "eagle-import:LED_SMD_SUNPLUS35_REVERSED")
      (libsource (lib "eagle-import") (part "LED_SMD_SUNPLUS35_REVERSED"))
    )
    (comp (ref "LD358DR")
      (value "L1SP-DRD00035R0000")
      (footprint "eagle-import:LED_SMD_SUNPLUS35_REVERSED")
      (libsource (lib "eagle-import") (part "LED_SMD_SUNPLUS35_REVERSED"))
    )
    (comp (ref "LD360DR")
      (value "L1SP-DRD00035R0000")
      (footprint "eagle-import:LED_SMD_SUNPLUS35_REVERSED")
      (libsource (lib "eagle-import") (part "LED_SMD_SUNPLUS35_REVERSED"))
    )
    (comp (ref "LD361DR")
      (value "L1SP-DRD00035R0000")
      (footprint "eagle-import:LED_SMD_SUNPLUS35_REVERSED")
      (libsource (lib "eagle-import") (part "LED_SMD_SUNPLUS35_REVERSED"))
    )
    (comp (ref "LD362DR")
      (value "L1SP-DRD00035R0000")
      (footprint "eagle-import:LED_SMD_SUNPLUS35_REVERSED")
      (libsource (lib "eagle-import") (part "LED_SMD_SUNPLUS35_REVERSED"))
    )
    (comp (ref "LD363DR")
      (value "L1SP-DRD00035R0000")
      (footprint "eagle-import:LED_SMD_SUNPLUS35_REVERSED")
      (libsource (lib "eagle-import") (part "LED_SMD_SUNPLUS35_REVERSED"))
    )
    (comp (ref "LD364DR")
      (value "L1SP-DRD00035R0000")
      (footprint "eagle-import:LED_SMD_SUNPLUS35_REVERSED")
      (libsource (lib "eagle-import") (part "LED_SMD_SUNPLUS35_REVERSED"))
    )
    (comp (ref "LD365DR")
      (value "L1SP-DRD00035R0000")
      (footprint "eagle-import:LED_SMD_SUNPLUS35_REVERSED")
      (libsource (lib "eagle-import") (part "LED_SMD_SUNPLUS35_REVERSED"))
    )
    (comp (ref "LD366DR")
      (value "L1SP-DRD00035R0000")
      (footprint "eagle-import:LED_SMD_SUNPLUS35_REVERSED")
      (libsource (lib "eagle-import") (part "LED_SMD_SUNPLUS35_REVERSED"))
    )
    (comp (ref "LD367DR")
      (value "L1SP-DRD00035R0000")
      (footprint "eagle-import:LED_SMD_SUNPLUS35_REVERSED")
      (libsource (lib "eagle-import") (part "LED_SMD_SUNPLUS35_REVERSED"))
    )
    (comp (ref "LD368DR")
      (value "L1SP-DRD00035R0000")
      (footprint "eagle-import:LED_SMD_SUNPLUS35_REVERSED")
      (libsource (lib "eagle-import") (part "LED_SMD_SUNPLUS35_REVERSED"))
    )
    (comp (ref "LD370DR")
      (value "L1SP-DRD00035R0000")
      (footprint "eagle-import:LED_SMD_SUNPLUS35_REVERSED")
      (libsource (lib "eagle-import") (part "LED_SMD_SUNPLUS35_REVERSED"))
    )
    (comp (ref "LD371DR")
      (value "L1SP-DRD00035R0000")
      (footprint "eagle-import:LED_SMD_SUNPLUS35_REVERSED")
      (libsource (lib "eagle-import") (part "LED_SMD_SUNPLUS35_REVERSED"))
    )
    (comp (ref "LD372DR")
      (value "L1SP-DRD00035R0000")
      (footprint "eagle-import:LED_SMD_SUNPLUS35_REVERSED")
      (libsource (lib "eagle-import") (part "LED_SMD_SUNPLUS35_REVERSED"))
    )
    (comp (ref "LD373DR")
      (value "L1SP-DRD00035R0000")
      (footprint "eagle-import:LED_SMD_SUNPLUS35_REVERSED")
      (libsource (lib "eagle-import") (part "LED_SMD_SUNPLUS35_REVERSED"))
    )
    (comp (ref "LD374DR")
      (value "L1SP-DRD00035R0000")
      (footprint "eagle-import:LED_SMD_SUNPLUS35_REVERSED")
      (libsource (lib "eagle-import") (part "LED_SMD_SUNPLUS35_REVERSED"))
    )
    (comp (ref "LD375DR")
      (value "L1SP-DRD00035R0000")
      (footprint "eagle-import:LED_SMD_SUNPLUS35_REVERSED")
      (libsource (lib "eagle-import") (part "LED_SMD_SUNPLUS35_REVERSED"))
    )
    (comp (ref "LD376DR")
      (value "L1SP-DRD00035R0000")
      (footprint "eagle-import:LED_SMD_SUNPLUS35_REVERSED")
      (libsource (lib "eagle-import") (part "LED_SMD_SUNPLUS35_REVERSED"))
    )
    (comp (ref "LD377DR")
      (value "L1SP-DRD00035R0000")
      (footprint "eagle-import:LED_SMD_SUNPLUS35_REVERSED")
      (libsource (lib "eagle-import") (part "LED_SMD_SUNPLUS35_REVERSED"))
    )
    (comp (ref "LD378DR")
      (value "L1SP-DRD00035R0000")
      (footprint "eagle-import:LED_SMD_SUNPLUS35_REVERSED")
      (libsource (lib "eagle-import") (part "LED_SMD_SUNPLUS35_REVERSED"))
    )
    (comp (ref "LD380DR")
      (value "L1SP-DRD00035R0000")
      (footprint "eagle-import:LED_SMD_SUNPLUS35_REVERSED")
      (libsource (lib "eagle-import") (part "LED_SMD_SUNPLUS35_REVERSED"))
    )
    (comp (ref "LD381DR")
      (value "L1SP-DRD00035R0000")
      (footprint "eagle-import:LED_SMD_SUNPLUS35_REVERSED")
      (libsource (lib "eagle-import") (part "LED_SMD_SUNPLUS35_REVERSED"))
    )
    (comp (ref "LD382DR")
      (value "L1SP-DRD00035R0000")
      (footprint "eagle-import:LED_SMD_SUNPLUS35_REVERSED")
      (libsource (lib "eagle-import") (part "LED_SMD_SUNPLUS35_REVERSED"))
    )
    (comp (ref "LD383DR")
      (value "L1SP-DRD00035R0000")
      (footprint "eagle-import:LED_SMD_SUNPLUS35_REVERSED")
      (libsource (lib "eagle-import") (part "LED_SMD_SUNPLUS35_REVERSED"))
    )
    (comp (ref "LD384DR")
      (value "L1SP-DRD00035R0000")
      (footprint "eagle-import:LED_SMD_SUNPLUS35_REVERSED")
      (libsource (lib "eagle-import") (part "LED_SMD_SUNPLUS35_REVERSED"))
    )
    (comp (ref "LD385DR")
      (value "L1SP-DRD00035R0000")
      (footprint "eagle-import:LED_SMD_SUNPLUS35_REVERSED")
      (libsource (lib "eagle-import") (part "LED_SMD_SUNPLUS35_REVERSED"))
    )
    (comp (ref "LD386DR")
      (value "L1SP-DRD00035R0000")
      (footprint "eagle-import:LED_SMD_SUNPLUS35_REVERSED")
      (libsource (lib "eagle-import") (part "LED_SMD_SUNPLUS35_REVERSED"))
    )
    (comp (ref "LD387DR")
      (value "L1SP-DRD00035R0000")
      (footprint "eagle-import:LED_SMD_SUNPLUS35_REVERSED")
      (libsource (lib "eagle-import") (part "LED_SMD_SUNPLUS35_REVERSED"))
    )
    (comp (ref "LD388DR")
      (value "L1SP-DRD00035R0000")
      (footprint "eagle-import:LED_SMD_SUNPLUS35_REVERSED")
      (libsource (lib "eagle-import") (part "LED_SMD_SUNPLUS35_REVERSED"))
    )
    (comp (ref "LD390DR")
      (value "L1SP-DRD00035R0000")
      (footprint "eagle-import:LED_SMD_SUNPLUS35_REVERSED")
      (libsource (lib "eagle-import") (part "LED_SMD_SUNPLUS35_REVERSED"))
    )
    (comp (ref "LD391DR")
      (value "L1SP-DRD00035R0000")
      (footprint "eagle-import:LED_SMD_SUNPLUS35_REVERSED")
      (libsource (lib "eagle-import") (part "LED_SMD_SUNPLUS35_REVERSED"))
    )
    (comp (ref "LD392DR")
      (value "L1SP-DRD00035R0000")
      (footprint "eagle-import:LED_SMD_SUNPLUS35_REVERSED")
      (libsource (lib "eagle-import") (part "LED_SMD_SUNPLUS35_REVERSED"))
    )
    (comp (ref "LD393DR")
      (value "L1SP-DRD00035R0000")
      (footprint "eagle-import:LED_SMD_SUNPLUS35_REVERSED")
      (libsource (lib "eagle-import") (part "LED_SMD_SUNPLUS35_REVERSED"))
    )
    (comp (ref "LD394DR")
      (value "L1SP-DRD00035R0000")
      (footprint "eagle-import:LED_SMD_SUNPLUS35_REVERSED")
      (libsource (lib "eagle-import") (part "LED_SMD_SUNPLUS35_REVERSED"))
    )
    (comp (ref "LD395DR")
      (value "L1SP-DRD00035R0000")
      (footprint "eagle-import:LED_SMD_SUNPLUS35_REVERSED")
      (libsource (lib "eagle-import") (part "LED_SMD_SUNPLUS35_REVERSED"))
    )
    (comp (ref "LD396DR")
      (value "L1SP-DRD00035R0000")
      (footprint "eagle-import:LED_SMD_SUNPLUS35_REVERSED")
      (libsource (lib "eagle-import") (part "LED_SMD_SUNPLUS35_REVERSED"))
    )
    (comp (ref "LD397DR")
      (value "L1SP-DRD00035R0000")
      (footprint "eagle-import:LED_SMD_SUNPLUS35_REVERSED")
      (libsource (lib "eagle-import") (part "LED_SMD_SUNPLUS35_REVERSED"))
    )
    (comp (ref "LD398DR")
      (value "L1SP-DRD00035R0000")
      (footprint "eagle-import:LED_SMD_SUNPLUS35_REVERSED")
      (libsource (lib "eagle-import") (part "LED_SMD_SUNPLUS35_REVERSED"))
    )
  )
  (nets
    (net (code "1") (name "GND") (class "Default")
      (node (ref "H11") (pin "P") (pinfunction "P_P") (pintype "bidirectional"))
      (node (ref "NTC") (pin "1") (pinfunction "1_1") (pintype "passive"))
    )
    (net (code "2") (name "Net-(LD3A0DR--)") (class "Default")
      (node (ref "H18") (pin "P") (pinfunction "P_P") (pintype "bidirectional"))
      (node (ref "LD3A0DR") (pin "A") (pinfunction "-_A") (pintype "passive"))
      (node (ref "LD3A1DR") (pin "A") (pinfunction "-_A") (pintype "passive"))
      (node (ref "LD3A2DR") (pin "A") (pinfunction "-_A") (pintype "passive"))
    )
    (net (code "3") (name "Net-(LD3A3DR--)") (class "Default")
      (node (ref "H20") (pin "P") (pinfunction "P_P") (pintype "bidirectional"))
      (node (ref "LD3A3DR") (pin "A") (pinfunction "-_A") (pintype "passive"))
      (node (ref "LD3A4DR") (pin "A") (pinfunction "-_A") (pintype "passive"))
      (node (ref "LD3A5DR") (pin "A") (pinfunction "-_A") (pintype "passive"))
    )
    (net (code "4") (name "Net-(LD3A6DR--)") (class "Default")
      (node (ref "H22") (pin "P") (pinfunction "P_P") (pintype "bidirectional"))
      (node (ref "LD3A6DR") (pin "A") (pinfunction "-_A") (pintype "passive"))
      (node (ref "LD3A7DR") (pin "A") (pinfunction "-_A") (pintype "passive"))
      (node (ref "LD3A8DR") (pin "A") (pinfunction "-_A") (pintype "passive"))
    )
    (net (code "5") (name "Net-(LD5A0FR--)") (class "Default")
      (node (ref "H26") (pin "P") (pinfunction "P_P") (pintype "bidirectional"))
      (node (ref "LD5A0FR") (pin "A") (pinfunction "-_A") (pintype "passive"))
      (node (ref "LD5A1FR") (pin "A") (pinfunction "-_A") (pintype "passive"))
    )
    (net (code "6") (name "Net-(LD300DR-+)") (class "Default")
      (node (ref "H17") (pin "P") (pinfunction "P_P") (pintype "bidirectional"))
      (node (ref "LD300DR") (pin "C") (pinfunction "+_C") (pintype "passive"))
      (node (ref "LD301DR") (pin "C") (pinfunction "+_C") (pintype "passive"))
      (node (ref "LD302DR") (pin "C") (pinfunction "+_C") (pintype "passive"))
    )
    (net (code "7") (name "Net-(LD300DR--)") (class "Default")
      (node (ref "LD300DR") (pin "A") (pinfunction "-_A") (pintype "passive"))
      (node (ref "LD310DR") (pin "C") (pinfunction "+_C") (pintype "passive"))
    )
    (net (code "8") (name "Net-(LD301DR--)") (class "Default")
      (node (ref "LD301DR") (pin "A") (pinfunction "-_A") (pintype "passive"))
      (node (ref "LD311DR") (pin "C") (pinfunction "+_C") (pintype "passive"))
    )
    (net (code "9") (name "Net-(LD302DR--)") (class "Default")
      (node (ref "LD302DR") (pin "A") (pinfunction "-_A") (pintype "passive"))
      (node (ref "LD312DR") (pin "C") (pinfunction "+_C") (pintype "passive"))
    )
    (net (code "10") (name "Net-(LD303DR-+)") (class "Default")
      (node (ref "H19") (pin "P") (pinfunction "P_P") (pintype "bidirectional"))
      (node (ref "LD303DR") (pin "C") (pinfunction "+_C") (pintype "passive"))
      (node (ref "LD304DR") (pin "C") (pinfunction "+_C") (pintype "passive"))
      (node (ref "LD305DR") (pin "C") (pinfunction "+_C") (pintype "passive"))
    )
    (net (code "11") (name "Net-(LD303DR--)") (class "Default")
      (node (ref "LD303DR") (pin "A") (pinfunction "-_A") (pintype "passive"))
      (node (ref "LD313DR") (pin "C") (pinfunction "+_C") (pintype "passive"))
    )
    (net (code "12") (name "Net-(LD304DR--)") (class "Default")
      (node (ref "LD304DR") (pin "A") (pinfunction "-_A") (pintype "passive"))
      (node (ref "LD314DR") (pin "C") (pinfunction "+_C") (pintype "passive"))
    )
    (net (code "13") (name "Net-(LD305DR--)") (class "Default")
      (node (ref "LD305DR") (pin "A") (pinfunction "-_A") (pintype "passive"))
      (node (ref "LD315DR") (pin "C") (pinfunction "+_C") (pintype "passive"))
    )
    (net (code "14") (name "Net-(LD306DR-+)") (class "Default")
      (node (ref "H21") (pin "P") (pinfunction "P_P") (pintype "bidirectional"))
      (node (ref "LD306DR") (pin "C") (pinfunction "+_C") (pintype "passive"))
      (node (ref "LD307DR") (pin "C") (pinfunction "+_C") (pintype "passive"))
      (node (ref "LD308DR") (pin "C") (pinfunction "+_C") (pintype "passive"))
    )
    (net (code "15") (name "Net-(LD306DR--)") (class "Default")
      (node (ref "LD306DR") (pin "A") (pinfunction "-_A") (pintype "passive"))
      (node (ref "LD316DR") (pin "C") (pinfunction "+_C") (pintype "passive"))
    )
    (net (code "16") (name "Net-(LD307DR--)") (class "Default")
      (node (ref "LD307DR") (pin "A") (pinfunction "-_A") (pintype "passive"))
      (node (ref "LD317DR") (pin "C") (pinfunction "+_C") (pintype "passive"))
    )
    (net (code "17") (name "Net-(LD308DR--)") (class "Default")
      (node (ref "LD308DR") (pin "A") (pinfunction "-_A") (pintype "passive"))
      (node (ref "LD318DR") (pin "C") (pinfunction "+_C") (pintype "passive"))
    )
    (net (code "18") (name "Net-(LD310DR--)") (class "Default")
      (node (ref "LD310DR") (pin "A") (pinfunction "-_A") (pintype "passive"))
      (node (ref "LD320DR") (pin "C") (pinfunction "+_C") (pintype "passive"))
    )
    (net (code "19") (name "Net-(LD311DR--)") (class "Default")
      (node (ref "LD311DR") (pin "A") (pinfunction "-_A") (pintype "passive"))
      (node (ref "LD321DR") (pin "C") (pinfunction "+_C") (pintype "passive"))
    )
    (net (code "20") (name "Net-(LD312DR--)") (class "Default")
      (node (ref "LD312DR") (pin "A") (pinfunction "-_A") (pintype "passive"))
      (node (ref "LD322DR") (pin "C") (pinfunction "+_C") (pintype "passive"))
    )
    (net (code "21") (name "Net-(LD313DR--)") (class "Default")
      (node (ref "LD313DR") (pin "A") (pinfunction "-_A") (pintype "passive"))
      (node (ref "LD323DR") (pin "C") (pinfunction "+_C") (pintype "passive"))
    )
    (net (code "22") (name "Net-(LD314DR--)") (class "Default")
      (node (ref "LD314DR") (pin "A") (pinfunction "-_A") (pintype "passive"))
      (node (ref "LD324DR") (pin "C") (pinfunction "+_C") (pintype "passive"))
    )
    (net (code "23") (name "Net-(LD315DR--)") (class "Default")
      (node (ref "LD315DR") (pin "A") (pinfunction "-_A") (pintype "passive"))
      (node (ref "LD325DR") (pin "C") (pinfunction "+_C") (pintype "passive"))
    )
    (net (code "24") (name "Net-(LD316DR--)") (class "Default")
      (node (ref "LD316DR") (pin "A") (pinfunction "-_A") (pintype "passive"))
      (node (ref "LD326DR") (pin "C") (pinfunction "+_C") (pintype "passive"))
    )
    (net (code "25") (name "Net-(LD317DR--)") (class "Default")
      (node (ref "LD317DR") (pin "A") (pinfunction "-_A") (pintype "passive"))
      (node (ref "LD327DR") (pin "C") (pinfunction "+_C") (pintype "passive"))
    )
    (net (code "26") (name "Net-(LD318DR--)") (class "Default")
      (node (ref "LD318DR") (pin "A") (pinfunction "-_A") (pintype "passive"))
      (node (ref "LD328DR") (pin "C") (pinfunction "+_C") (pintype "passive"))
    )
    (net (code "27") (name "Net-(LD320DR--)") (class "Default")
      (node (ref "LD320DR") (pin "A") (pinfunction "-_A") (pintype "passive"))
      (node (ref "LD330DR") (pin "C") (pinfunction "+_C") (pintype "passive"))
    )
    (net (code "28") (name "Net-(LD321DR--)") (class "Default")
      (node (ref "LD321DR") (pin "A") (pinfunction "-_A") (pintype "passive"))
      (node (ref "LD331DR") (pin "C") (pinfunction "+_C") (pintype "passive"))
    )
    (net (code "29") (name "Net-(LD322DR--)") (class "Default")
      (node (ref "LD322DR") (pin "A") (pinfunction "-_A") (pintype "passive"))
      (node (ref "LD332DR") (pin "C") (pinfunction "+_C") (pintype "passive"))
    )
    (net (code "30") (name "Net-(LD323DR--)") (class "Default")
      (node (ref "LD323DR") (pin "A") (pinfunction "-_A") (pintype "passive"))
      (node (ref "LD333DR") (pin "C") (pinfunction "+_C") (pintype "passive"))
    )
    (net (code "31") (name "Net-(LD324DR--)") (class "Default")
      (node (ref "LD324DR") (pin "A") (pinfunction "-_A") (pintype "passive"))
      (node (ref "LD334DR") (pin "C") (pinfunction "+_C") (pintype "passive"))
    )
    (net (code "32") (name "Net-(LD325DR--)") (class "Default")
      (node (ref "LD325DR") (pin "A") (pinfunction "-_A") (pintype "passive"))
      (node (ref "LD335DR") (pin "C") (pinfunction "+_C") (pintype "passive"))
    )
    (net (code "33") (name "Net-(LD326DR--)") (class "Default")
      (node (ref "LD326DR") (pin "A") (pinfunction "-_A") (pintype "passive"))
      (node (ref "LD336DR") (pin "C") (pinfunction "+_C") (pintype "passive"))
    )
    (net (code "34") (name "Net-(LD327DR--)") (class "Default")
      (node (ref "LD327DR") (pin "A") (pinfunction "-_A") (pintype "passive"))
      (node (ref "LD337DR") (pin "C") (pinfunction "+_C") (pintype "passive"))
    )
    (net (code "35") (name "Net-(LD328DR--)") (class "Default")
      (node (ref "LD328DR") (pin "A") (pinfunction "-_A") (pintype "passive"))
      (node (ref "LD338DR") (pin "C") (pinfunction "+_C") (pintype "passive"))
    )
    (net (code "36") (name "Net-(LD330DR--)") (class "Default")
      (node (ref "LD330DR") (pin "A") (pinfunction "-_A") (pintype "passive"))
      (node (ref "LD340DR") (pin "C") (pinfunction "+_C") (pintype "passive"))
    )
    (net (code "37") (name "Net-(LD331DR--)") (class "Default")
      (node (ref "LD331DR") (pin "A") (pinfunction "-_A") (pintype "passive"))
      (node (ref "LD341DR") (pin "C") (pinfunction "+_C") (pintype "passive"))
    )
    (net (code "38") (name "Net-(LD332DR--)") (class "Default")
      (node (ref "LD332DR") (pin "A") (pinfunction "-_A") (pintype "passive"))
      (node (ref "LD342DR") (pin "C") (pinfunction "+_C") (pintype "passive"))
    )
    (net (code "39") (name "Net-(LD333DR--)") (class "Default")
      (node (ref "LD333DR") (pin "A") (pinfunction "-_A") (pintype "passive"))
      (node (ref "LD343DR") (pin "C") (pinfunction "+_C") (pintype "passive"))
    )
    (net (code "40") (name "Net-(LD334DR--)") (class "Default")
      (node (ref "LD334DR") (pin "A") (pinfunction "-_A") (pintype "passive"))
      (node (ref "LD344DR") (pin "C") (pinfunction "+_C") (pintype "passive"))
    )
    (net (code "41") (name "Net-(LD335DR--)") (class "Default")
      (node (ref "LD335DR") (pin "A") (pinfunction "-_A") (pintype "passive"))
      (node (ref "LD345DR") (pin "C") (pinfunction "+_C") (pintype "passive"))
    )
    (net (code "42") (name "Net-(LD336DR--)") (class "Default")
      (node (ref "LD336DR") (pin "A") (pinfunction "-_A") (pintype "passive"))
      (node (ref "LD346DR") (pin "C") (pinfunction "+_C") (pintype "passive"))
    )
    (net (code "43") (name "Net-(LD337DR--)") (class "Default")
      (node (ref "LD337DR") (pin "A") (pinfunction "-_A") (pintype "passive"))
      (node (ref "LD347DR") (pin "C") (pinfunction "+_C") (pintype "passive"))
    )
    (net (code "44") (name "Net-(LD338DR--)") (class "Default")
      (node (ref "LD338DR") (pin "A") (pinfunction "-_A") (pintype "passive"))
      (node (ref "LD348DR") (pin "C") (pinfunction "+_C") (pintype "passive"))
    )
    (net (code "45") (name "Net-(LD340DR--)") (class "Default")
      (node (ref "LD340DR") (pin "A") (pinfunction "-_A") (pintype "passive"))
      (node (ref "LD350DR") (pin "C") (pinfunction "+_C") (pintype "passive"))
    )
    (net (code "46") (name "Net-(LD341DR--)") (class "Default")
      (node (ref "LD341DR") (pin "A") (pinfunction "-_A") (pintype "passive"))
      (node (ref "LD351DR") (pin "C") (pinfunction "+_C") (pintype "passive"))
    )
    (net (code "47") (name "Net-(LD342DR--)") (class "Default")
      (node (ref "LD342DR") (pin "A") (pinfunction "-_A") (pintype "passive"))
      (node (ref "LD352DR") (pin "C") (pinfunction "+_C") (pintype "passive"))
    )
    (net (code "48") (name "Net-(LD343DR--)") (class "Default")
      (node (ref "LD343DR") (pin "A") (pinfunction "-_A") (pintype "passive"))
      (node (ref "LD353DR") (pin "C") (pinfunction "+_C") (pintype "passive"))
    )
    (net (code "49") (name "Net-(LD344DR--)") (class "Default")
      (node (ref "LD344DR") (pin "A") (pinfunction "-_A") (pintype "passive"))
      (node (ref "LD354DR") (pin "C") (pinfunction "+_C") (pintype "passive"))
    )
    (net (code "50") (name "Net-(LD345DR--)") (class "Default")
      (node (ref "LD345DR") (pin "A") (pinfunction "-_A") (pintype "passive"))
      (node (ref "LD355DR") (pin "C") (pinfunction "+_C") (pintype "passive"))
    )
    (net (code "51") (name "Net-(LD346DR--)") (class "Default")
      (node (ref "LD346DR") (pin "A") (pinfunction "-_A") (pintype "passive"))
      (node (ref "LD356DR") (pin "C") (pinfunction "+_C") (pintype "passive"))
    )
    (net (code "52") (name "Net-(LD347DR--)") (class "Default")
      (node (ref "LD347DR") (pin "A") (pinfunction "-_A") (pintype "passive"))
      (node (ref "LD357DR") (pin "C") (pinfunction "+_C") (pintype "passive"))
    )
    (net (code "53") (name "Net-(LD348DR--)") (class "Default")
      (node (ref "LD348DR") (pin "A") (pinfunction "-_A") (pintype "passive"))
      (node (ref "LD358DR") (pin "C") (pinfunction "+_C") (pintype "passive"))
    )
    (net (code "54") (name "Net-(LD350DR--)") (class "Default")
      (node (ref "LD350DR") (pin "A") (pinfunction "-_A") (pintype "passive"))
      (node (ref "LD360DR") (pin "C") (pinfunction "+_C") (pintype "passive"))
    )
    (net (code "55") (name "Net-(LD351DR--)") (class "Default")
      (node (ref "LD351DR") (pin "A") (pinfunction "-_A") (pintype "passive"))
      (node (ref "LD361DR") (pin "C") (pinfunction "+_C") (pintype "passive"))
    )
    (net (code "56") (name "Net-(LD352DR--)") (class "Default")
      (node (ref "LD352DR") (pin "A") (pinfunction "-_A") (pintype "passive"))
      (node (ref "LD362DR") (pin "C") (pinfunction "+_C") (pintype "passive"))
    )
    (net (code "57") (name "Net-(LD353DR--)") (class "Default")
      (node (ref "LD353DR") (pin "A") (pinfunction "-_A") (pintype "passive"))
      (node (ref "LD363DR") (pin "C") (pinfunction "+_C") (pintype "passive"))
    )
    (net (code "58") (name "Net-(LD354DR--)") (class "Default")
      (node (ref "LD354DR") (pin "A") (pinfunction "-_A") (pintype "passive"))
      (node (ref "LD364DR") (pin "C") (pinfunction "+_C") (pintype "passive"))
    )
    (net (code "59") (name "Net-(LD355DR--)") (class "Default")
      (node (ref "LD355DR") (pin "A") (pinfunction "-_A") (pintype "passive"))
      (node (ref "LD365DR") (pin "C") (pinfunction "+_C") (pintype "passive"))
    )
    (net (code "60") (name "Net-(LD356DR--)") (class "Default")
      (node (ref "LD356DR") (pin "A") (pinfunction "-_A") (pintype "passive"))
      (node (ref "LD366DR") (pin "C") (pinfunction "+_C") (pintype "passive"))
    )
    (net (code "61") (name "Net-(LD357DR--)") (class "Default")
      (node (ref "LD357DR") (pin "A") (pinfunction "-_A") (pintype "passive"))
      (node (ref "LD367DR") (pin "C") (pinfunction "+_C") (pintype "passive"))
    )
    (net (code "62") (name "Net-(LD358DR--)") (class "Default")
      (node (ref "LD358DR") (pin "A") (pinfunction "-_A") (pintype "passive"))
      (node (ref "LD368DR") (pin "C") (pinfunction "+_C") (pintype "passive"))
    )
    (net (code "63") (name "Net-(LD360DR--)") (class "Default")
      (node (ref "LD360DR") (pin "A") (pinfunction "-_A") (pintype "passive"))
      (node (ref "LD370DR") (pin "C") (pinfunction "+_C") (pintype "passive"))
    )
    (net (code "64") (name "Net-(LD361DR--)") (class "Default")
      (node (ref "LD361DR") (pin "A") (pinfunction "-_A") (pintype "passive"))
      (node (ref "LD371DR") (pin "C") (pinfunction "+_C") (pintype "passive"))
    )
    (net (code "65") (name "Net-(LD362DR--)") (class "Default")
      (node (ref "LD362DR") (pin "A") (pinfunction "-_A") (pintype "passive"))
      (node (ref "LD372DR") (pin "C") (pinfunction "+_C") (pintype "passive"))
    )
    (net (code "66") (name "Net-(LD363DR--)") (class "Default")
      (node (ref "LD363DR") (pin "A") (pinfunction "-_A") (pintype "passive"))
      (node (ref "LD373DR") (pin "C") (pinfunction "+_C") (pintype "passive"))
    )
    (net (code "67") (name "Net-(LD364DR--)") (class "Default")
      (node (ref "LD364DR") (pin "A") (pinfunction "-_A") (pintype "passive"))
      (node (ref "LD374DR") (pin "C") (pinfunction "+_C") (pintype "passive"))
    )
    (net (code "68") (name "Net-(LD365DR--)") (class "Default")
      (node (ref "LD365DR") (pin "A") (pinfunction "-_A") (pintype "passive"))
      (node (ref "LD375DR") (pin "C") (pinfunction "+_C") (pintype "passive"))
    )
    (net (code "69") (name "Net-(LD366DR--)") (class "Default")
      (node (ref "LD366DR") (pin "A") (pinfunction "-_A") (pintype "passive"))
      (node (ref "LD376DR") (pin "C") (pinfunction "+_C") (pintype "passive"))
    )
    (net (code "70") (name "Net-(LD367DR--)") (class "Default")
      (node (ref "LD367DR") (pin "A") (pinfunction "-_A") (pintype "passive"))
      (node (ref "LD377DR") (pin "C") (pinfunction "+_C") (pintype "passive"))
    )
    (net (code "71") (name "Net-(LD368DR--)") (class "Default")
      (node (ref "LD368DR") (pin "A") (pinfunction "-_A") (pintype "passive"))
      (node (ref "LD378DR") (pin "C") (pinfunction "+_C") (pintype "passive"))
    )
    (net (code "72") (name "Net-(LD370DR--)") (class "Default")
      (node (ref "LD370DR") (pin "A") (pinfunction "-_A") (pintype "passive"))
      (node (ref "LD380DR") (pin "C") (pinfunction "+_C") (pintype "passive"))
    )
    (net (code "73") (name "Net-(LD371DR--)") (class "Default")
      (node (ref "LD371DR") (pin "A") (pinfunction "-_A") (pintype "passive"))
      (node (ref "LD381DR") (pin "C") (pinfunction "+_C") (pintype "passive"))
    )
    (net (code "74") (name "Net-(LD372DR--)") (class "Default")
      (node (ref "LD372DR") (pin "A") (pinfunction "-_A") (pintype "passive"))
      (node (ref "LD382DR") (pin "C") (pinfunction "+_C") (pintype "passive"))
    )
    (net (code "75") (name "Net-(LD373DR--)") (class "Default")
      (node (ref "LD373DR") (pin "A") (pinfunction "-_A") (pintype "passive"))
      (node (ref "LD383DR") (pin "C") (pinfunction "+_C") (pintype "passive"))
    )
    (net (code "76") (name "Net-(LD374DR--)") (class "Default")
      (node (ref "LD374DR") (pin "A") (pinfunction "-_A") (pintype "passive"))
      (node (ref "LD384DR") (pin "C") (pinfunction "+_C") (pintype "passive"))
    )
    (net (code "77") (name "Net-(LD375DR--)") (class "Default")
      (node (ref "LD375DR") (pin "A") (pinfunction "-_A") (pintype "passive"))
      (node (ref "LD385DR") (pin "C") (pinfunction "+_C") (pintype "passive"))
    )
    (net (code "78") (name "Net-(LD376DR--)") (class "Default")
      (node (ref "LD376DR") (pin "A") (pinfunction "-_A") (pintype "passive"))
      (node (ref "LD386DR") (pin "C") (pinfunction "+_C") (pintype "passive"))
    )
    (net (code "79") (name "Net-(LD377DR--)") (class "Default")
      (node (ref "LD377DR") (pin "A") (pinfunction "-_A") (pintype "passive"))
      (node (ref "LD387DR") (pin "C") (pinfunction "+_C") (pintype "passive"))
    )
    (net (code "80") (name "Net-(LD378DR--)") (class "Default")
      (node (ref "LD378DR") (pin "A") (pinfunction "-_A") (pintype "passive"))
      (node (ref "LD388DR") (pin "C") (pinfunction "+_C") (pintype "passive"))
    )
    (net (code "81") (name "Net-(LD380DR--)") (class "Default")
      (node (ref "LD380DR") (pin "A") (pinfunction "-_A") (pintype "passive"))
      (node (ref "LD390DR") (pin "C") (pinfunction "+_C") (pintype "passive"))
    )
    (net (code "82") (name "Net-(LD381DR--)") (class "Default")
      (node (ref "LD381DR") (pin "A") (pinfunction "-_A") (pintype "passive"))
      (node (ref "LD391DR") (pin "C") (pinfunction "+_C") (pintype "passive"))
    )
    (net (code "83") (name "Net-(LD382DR--)") (class "Default")
      (node (ref "LD382DR") (pin "A") (pinfunction "-_A") (pintype "passive"))
      (node (ref "LD392DR") (pin "C") (pinfunction "+_C") (pintype "passive"))
    )
    (net (code "84") (name "Net-(LD383DR--)") (class "Default")
      (node (ref "LD383DR") (pin "A") (pinfunction "-_A") (pintype "passive"))
      (node (ref "LD393DR") (pin "C") (pinfunction "+_C") (pintype "passive"))
    )
    (net (code "85") (name "Net-(LD384DR--)") (class "Default")
      (node (ref "LD384DR") (pin "A") (pinfunction "-_A") (pintype "passive"))
      (node (ref "LD394DR") (pin "C") (pinfunction "+_C") (pintype "passive"))
    )
    (net (code "86") (name "Net-(LD385DR--)") (class "Default")
      (node (ref "LD385DR") (pin "A") (pinfunction "-_A") (pintype "passive"))
      (node (ref "LD395DR") (pin "C") (pinfunction "+_C") (pintype "passive"))
    )
    (net (code "87") (name "Net-(LD386DR--)") (class "Default")
      (node (ref "LD386DR") (pin "A") (pinfunction "-_A") (pintype "passive"))
      (node (ref "LD396DR") (pin "C") (pinfunction "+_C") (pintype "passive"))
    )
    (net (code "88") (name "Net-(LD387DR--)") (class "Default")
      (node (ref "LD387DR") (pin "A") (pinfunction "-_A") (pintype "passive"))
      (node (ref "LD397DR") (pin "C") (pinfunction "+_C") (pintype "passive"))
    )
    (net (code "89") (name "Net-(LD388DR--)") (class "Default")
      (node (ref "LD388DR") (pin "A") (pinfunction "-_A") (pintype "passive"))
      (node (ref "LD398DR") (pin "C") (pinfunction "+_C") (pintype "passive"))
    )
    (net (code "90") (name "Net-(LD390DR--)") (class "Default")
      (node (ref "LD390DR") (pin "A") (pinfunction "-_A") (pintype "passive"))
      (node (ref "LD3A0DR") (pin "C") (pinfunction "+_C") (pintype "passive"))
    )
    (net (code "91") (name "Net-(LD391DR--)") (class "Default")
      (node (ref "LD391DR") (pin "A") (pinfunction "-_A") (pintype "passive"))
      (node (ref "LD3A1DR") (pin "C") (pinfunction "+_C") (pintype "passive"))
    )
    (net (code "92") (name "Net-(LD392DR--)") (class "Default")
      (node (ref "LD392DR") (pin "A") (pinfunction "-_A") (pintype "passive"))
      (node (ref "LD3A2DR") (pin "C") (pinfunction "+_C") (pintype "passive"))
    )
    (net (code "93") (name "Net-(LD393DR--)") (class "Default")
      (node (ref "LD393DR") (pin "A") (pinfunction "-_A") (pintype "passive"))
      (node (ref "LD3A3DR") (pin "C") (pinfunction "+_C") (pintype "passive"))
    )
    (net (code "94") (name "Net-(LD394DR--)") (class "Default")
      (node (ref "LD394DR") (pin "A") (pinfunction "-_A") (pintype "passive"))
      (node (ref "LD3A4DR") (pin "C") (pinfunction "+_C") (pintype "passive"))
    )
    (net (code "95") (name "Net-(LD395DR--)") (class "Default")
      (node (ref "LD395DR") (pin "A") (pinfunction "-_A") (pintype "passive"))
      (node (ref "LD3A5DR") (pin "C") (pinfunction "+_C") (pintype "passive"))
    )
    (net (code "96") (name "Net-(LD396DR--)") (class "Default")
      (node (ref "LD396DR") (pin "A") (pinfunction "-_A") (pintype "passive"))
      (node (ref "LD3A6DR") (pin "C") (pinfunction "+_C") (pintype "passive"))
    )
    (net (code "97") (name "Net-(LD397DR--)") (class "Default")
      (node (ref "LD397DR") (pin "A") (pinfunction "-_A") (pintype "passive"))
      (node (ref "LD3A7DR") (pin "C") (pinfunction "+_C") (pintype "passive"))
    )
    (net (code "98") (name "Net-(LD398DR--)") (class "Default")
      (node (ref "LD398DR") (pin "A") (pinfunction "-_A") (pintype "passive"))
      (node (ref "LD3A8DR") (pin "C") (pinfunction "+_C") (pintype "passive"))
    )
    (net (code "99") (name "Net-(LD400B-+)") (class "Default")
      (node (ref "H23") (pin "P") (pinfunction "P_P") (pintype "bidirectional"))
      (node (ref "LD400B") (pin "A") (pinfunction "+_A") (pintype "passive"))
      (node (ref "LD401B") (pin "A") (pinfunction "+_A") (pintype "passive"))
      (node (ref "LD402B") (pin "A") (pinfunction "+_A") (pintype "passive"))
      (node (ref "LD403B") (pin "A") (pinfunction "+_A") (pintype "passive"))
    )
    (net (code "100") (name "Net-(LD400B--)") (class "Default")
      (node (ref "LD400B") (pin "C") (pinfunction "-_C") (pintype "passive"))
      (node (ref "LD410B") (pin "A") (pinfunction "+_A") (pintype "passive"))
    )
    (net (code "101") (name "Net-(LD401B--)") (class "Default")
      (node (ref "LD401B") (pin "C") (pinfunction "-_C") (pintype "passive"))
      (node (ref "LD411B") (pin "A") (pinfunction "+_A") (pintype "passive"))
    )
    (net (code "102") (name "Net-(LD402B--)") (class "Default")
      (node (ref "LD402B") (pin "C") (pinfunction "-_C") (pintype "passive"))
      (node (ref "LD412B") (pin "A") (pinfunction "+_A") (pintype "passive"))
    )
    (net (code "103") (name "Net-(LD403B--)") (class "Default")
      (node (ref "LD403B") (pin "C") (pinfunction "-_C") (pintype "passive"))
      (node (ref "LD413B") (pin "A") (pinfunction "+_A") (pintype "passive"))
    )
    (net (code "104") (name "Net-(LD410B--)") (class "Default")
      (node (ref "LD410B") (pin "C") (pinfunction "-_C") (pintype "passive"))
      (node (ref "LD420B") (pin "A") (pinfunction "+_A") (pintype "passive"))
    )
    (net (code "105") (name "Net-(LD411B--)") (class "Default")
      (node (ref "LD411B") (pin "C") (pinfunction "-_C") (pintype "passive"))
      (node (ref "LD421B") (pin "A") (pinfunction "+_A") (pintype "passive"))
    )
    (net (code "106") (name "Net-(LD412B--)") (class "Default")
      (node (ref "LD412B") (pin "C") (pinfunction "-_C") (pintype "passive"))
      (node (ref "LD422B") (pin "A") (pinfunction "+_A") (pintype "passive"))
    )
    (net (code "107") (name "Net-(LD413B--)") (class "Default")
      (node (ref "LD413B") (pin "C") (pinfunction "-_C") (pintype "passive"))
      (node (ref "LD423B") (pin "A") (pinfunction "+_A") (pintype "passive"))
    )
    (net (code "108") (name "Net-(LD420B--)") (class "Default")
      (node (ref "LD420B") (pin "C") (pinfunction "-_C") (pintype "passive"))
      (node (ref "LD430B") (pin "A") (pinfunction "+_A") (pintype "passive"))
    )
    (net (code "109") (name "Net-(LD421B--)") (class "Default")
      (node (ref "LD421B") (pin "C") (pinfunction "-_C") (pintype "passive"))
      (node (ref "LD431B") (pin "A") (pinfunction "+_A") (pintype "passive"))
    )
    (net (code "110") (name "Net-(LD422B--)") (class "Default")
      (node (ref "LD422B") (pin "C") (pinfunction "-_C") (pintype "passive"))
      (node (ref "LD432B") (pin "A") (pinfunction "+_A") (pintype "passive"))
    )
    (net (code "111") (name "Net-(LD423B--)") (class "Default")
      (node (ref "LD423B") (pin "C") (pinfunction "-_C") (pintype "passive"))
      (node (ref "LD433B") (pin "A") (pinfunction "+_A") (pintype "passive"))
    )
    (net (code "112") (name "Net-(LD430B--)") (class "Default")
      (node (ref "LD430B") (pin "C") (pinfunction "-_C") (pintype "passive"))
      (node (ref "LD440B") (pin "A") (pinfunction "+_A") (pintype "passive"))
    )
    (net (code "113") (name "Net-(LD431B--)") (class "Default")
      (node (ref "LD431B") (pin "C") (pinfunction "-_C") (pintype "passive"))
      (node (ref "LD441B") (pin "A") (pinfunction "+_A") (pintype "passive"))
    )
    (net (code "114") (name "Net-(LD432B--)") (class "Default")
      (node (ref "LD432B") (pin "C") (pinfunction "-_C") (pintype "passive"))
      (node (ref "LD442B") (pin "A") (pinfunction "+_A") (pintype "passive"))
    )
    (net (code "115") (name "Net-(LD433B--)") (class "Default")
      (node (ref "LD433B") (pin "C") (pinfunction "-_C") (pintype "passive"))
      (node (ref "LD443B") (pin "A") (pinfunction "+_A") (pintype "passive"))
    )
    (net (code "116") (name "Net-(LD440B--)") (class "Default")
      (node (ref "LD440B") (pin "C") (pinfunction "-_C") (pintype "passive"))
      (node (ref "LD450B") (pin "A") (pinfunction "+_A") (pintype "passive"))
    )
    (net (code "117") (name "Net-(LD441B--)") (class "Default")
      (node (ref "LD441B") (pin "C") (pinfunction "-_C") (pintype "passive"))
      (node (ref "LD451B") (pin "A") (pinfunction "+_A") (pintype "passive"))
    )
    (net (code "118") (name "Net-(LD442B--)") (class "Default")
      (node (ref "LD442B") (pin "C") (pinfunction "-_C") (pintype "passive"))
      (node (ref "LD452B") (pin "A") (pinfunction "+_A") (pintype "passive"))
    )
    (net (code "119") (name "Net-(LD443B--)") (class "Default")
      (node (ref "LD443B") (pin "C") (pinfunction "-_C") (pintype "passive"))
      (node (ref "LD453B") (pin "A") (pinfunction "+_A") (pintype "passive"))
    )
    (net (code "120") (name "Net-(LD450B--)") (class "Default")
      (node (ref "LD450B") (pin "C") (pinfunction "-_C") (pintype "passive"))
      (node (ref "LD460B") (pin "A") (pinfunction "+_A") (pintype "passive"))
    )
    (net (code "121") (name "Net-(LD451B--)") (class "Default")
      (node (ref "LD451B") (pin "C") (pinfunction "-_C") (pintype "passive"))
      (node (ref "LD461B") (pin "A") (pinfunction "+_A") (pintype "passive"))
    )
    (net (code "122") (name "Net-(LD452B--)") (class "Default")
      (node (ref "LD452B") (pin "C") (pinfunction "-_C") (pintype "passive"))
      (node (ref "LD462B") (pin "A") (pinfunction "+_A") (pintype "passive"))
    )
    (net (code "123") (name "Net-(LD453B--)") (class "Default")
      (node (ref "LD453B") (pin "C") (pinfunction "-_C") (pintype "passive"))
      (node (ref "LD463B") (pin "A") (pinfunction "+_A") (pintype "passive"))
    )
    (net (code "124") (name "Net-(LD460B--)") (class "Default")
      (node (ref "H24") (pin "P") (pinfunction "P_P") (pintype "bidirectional"))
      (node (ref "H28") (pin "P") (pinfunction "P_P") (pintype "bidirectional"))
      (node (ref "LD460B") (pin "C") (pinfunction "-_C") (pintype "passive"))
      (node (ref "LD461B") (pin "C") (pinfunction "-_C") (pintype "passive"))
      (node (ref "LD462B") (pin "C") (pinfunction "-_C") (pintype "passive"))
      (node (ref "LD463B") (pin "C") (pinfunction "-_C") (pintype "passive"))
    )
    (net (code "125") (name "Net-(LD500FR-+)") (class "Default")
      (node (ref "H25") (pin "P") (pinfunction "P_P") (pintype "bidirectional"))
      (node (ref "H27") (pin "P") (pinfunction "P_P") (pintype "bidirectional"))
      (node (ref "LD500FR") (pin "C") (pinfunction "+_C") (pintype "passive"))
      (node (ref "LD501FR") (pin "C") (pinfunction "+_C") (pintype "passive"))
    )
    (net (code "126") (name "Net-(LD500FR--)") (class "Default")
      (node (ref "LD500FR") (pin "A") (pinfunction "-_A") (pintype "passive"))
      (node (ref "LD510FR") (pin "C") (pinfunction "+_C") (pintype "passive"))
    )
    (net (code "127") (name "Net-(LD501FR--)") (class "Default")
      (node (ref "LD501FR") (pin "A") (pinfunction "-_A") (pintype "passive"))
      (node (ref "LD511FR") (pin "C") (pinfunction "+_C") (pintype "passive"))
    )
    (net (code "128") (name "Net-(LD510FR--)") (class "Default")
      (node (ref "LD510FR") (pin "A") (pinfunction "-_A") (pintype "passive"))
      (node (ref "LD520FR") (pin "C") (pinfunction "+_C") (pintype "passive"))
    )
    (net (code "129") (name "Net-(LD511FR--)") (class "Default")
      (node (ref "LD511FR") (pin "A") (pinfunction "-_A") (pintype "passive"))
      (node (ref "LD521FR") (pin "C") (pinfunction "+_C") (pintype "passive"))
    )
    (net (code "130") (name "Net-(LD520FR--)") (class "Default")
      (node (ref "LD520FR") (pin "A") (pinfunction "-_A") (pintype "passive"))
      (node (ref "LD530FR") (pin "C") (pinfunction "+_C") (pintype "passive"))
    )
    (net (code "131") (name "Net-(LD521FR--)") (class "Default")
      (node (ref "LD521FR") (pin "A") (pinfunction "-_A") (pintype "passive"))
      (node (ref "LD531FR") (pin "C") (pinfunction "+_C") (pintype "passive"))
    )
    (net (code "132") (name "Net-(LD530FR--)") (class "Default")
      (node (ref "LD530FR") (pin "A") (pinfunction "-_A") (pintype "passive"))
      (node (ref "LD540FR") (pin "C") (pinfunction "+_C") (pintype "passive"))
    )
    (net (code "133") (name "Net-(LD531FR--)") (class "Default")
      (node (ref "LD531FR") (pin "A") (pinfunction "-_A") (pintype "passive"))
      (node (ref "LD541FR") (pin "C") (pinfunction "+_C") (pintype "passive"))
    )
    (net (code "134") (name "Net-(LD540FR--)") (class "Default")
      (node (ref "LD540FR") (pin "A") (pinfunction "-_A") (pintype "passive"))
      (node (ref "LD550FR") (pin "C") (pinfunction "+_C") (pintype "passive"))
    )
    (net (code "135") (name "Net-(LD541FR--)") (class "Default")
      (node (ref "LD541FR") (pin "A") (pinfunction "-_A") (pintype "passive"))
      (node (ref "LD551FR") (pin "C") (pinfunction "+_C") (pintype "passive"))
    )
    (net (code "136") (name "Net-(LD550FR--)") (class "Default")
      (node (ref "LD550FR") (pin "A") (pinfunction "-_A") (pintype "passive"))
      (node (ref "LD560FR") (pin "C") (pinfunction "+_C") (pintype "passive"))
    )
    (net (code "137") (name "Net-(LD551FR--)") (class "Default")
      (node (ref "LD551FR") (pin "A") (pinfunction "-_A") (pintype "passive"))
      (node (ref "LD561FR") (pin "C") (pinfunction "+_C") (pintype "passive"))
    )
    (net (code "138") (name "Net-(LD560FR--)") (class "Default")
      (node (ref "LD560FR") (pin "A") (pinfunction "-_A") (pintype "passive"))
      (node (ref "LD570FR") (pin "C") (pinfunction "+_C") (pintype "passive"))
    )
    (net (code "139") (name "Net-(LD561FR--)") (class "Default")
      (node (ref "LD561FR") (pin "A") (pinfunction "-_A") (pintype "passive"))
      (node (ref "LD571FR") (pin "C") (pinfunction "+_C") (pintype "passive"))
    )
    (net (code "140") (name "Net-(LD570FR--)") (class "Default")
      (node (ref "LD570FR") (pin "A") (pinfunction "-_A") (pintype "passive"))
      (node (ref "LD580FR") (pin "C") (pinfunction "+_C") (pintype "passive"))
    )
    (net (code "141") (name "Net-(LD571FR--)") (class "Default")
      (node (ref "LD571FR") (pin "A") (pinfunction "-_A") (pintype "passive"))
      (node (ref "LD581FR") (pin "C") (pinfunction "+_C") (pintype "passive"))
    )
    (net (code "142") (name "Net-(LD580FR--)") (class "Default")
      (node (ref "LD580FR") (pin "A") (pinfunction "-_A") (pintype "passive"))
      (node (ref "LD590FR") (pin "C") (pinfunction "+_C") (pintype "passive"))
    )
    (net (code "143") (name "Net-(LD581FR--)") (class "Default")
      (node (ref "LD581FR") (pin "A") (pinfunction "-_A") (pintype "passive"))
      (node (ref "LD591FR") (pin "C") (pinfunction "+_C") (pintype "passive"))
    )
    (net (code "144") (name "Net-(LD590FR--)") (class "Default")
      (node (ref "LD590FR") (pin "A") (pinfunction "-_A") (pintype "passive"))
      (node (ref "LD5A0FR") (pin "C") (pinfunction "+_C") (pintype "passive"))
    )
    (net (code "145") (name "Net-(LD591FR--)") (class "Default")
      (node (ref "LD591FR") (pin "A") (pinfunction "-_A") (pintype "passive"))
      (node (ref "LD5A1FR") (pin "C") (pinfunction "+_C") (pintype "passive"))
    )
    (net (code "146") (name "TEMP") (class "Default")
      (node (ref "H12") (pin "P") (pinfunction "P_P") (pintype "bidirectional"))
      (node (ref "NTC") (pin "2") (pinfunction "2_2") (pintype "passive"))
    )
  )
)
